# orig.net
KiCad netlist of a schematic drawn in EAGLE
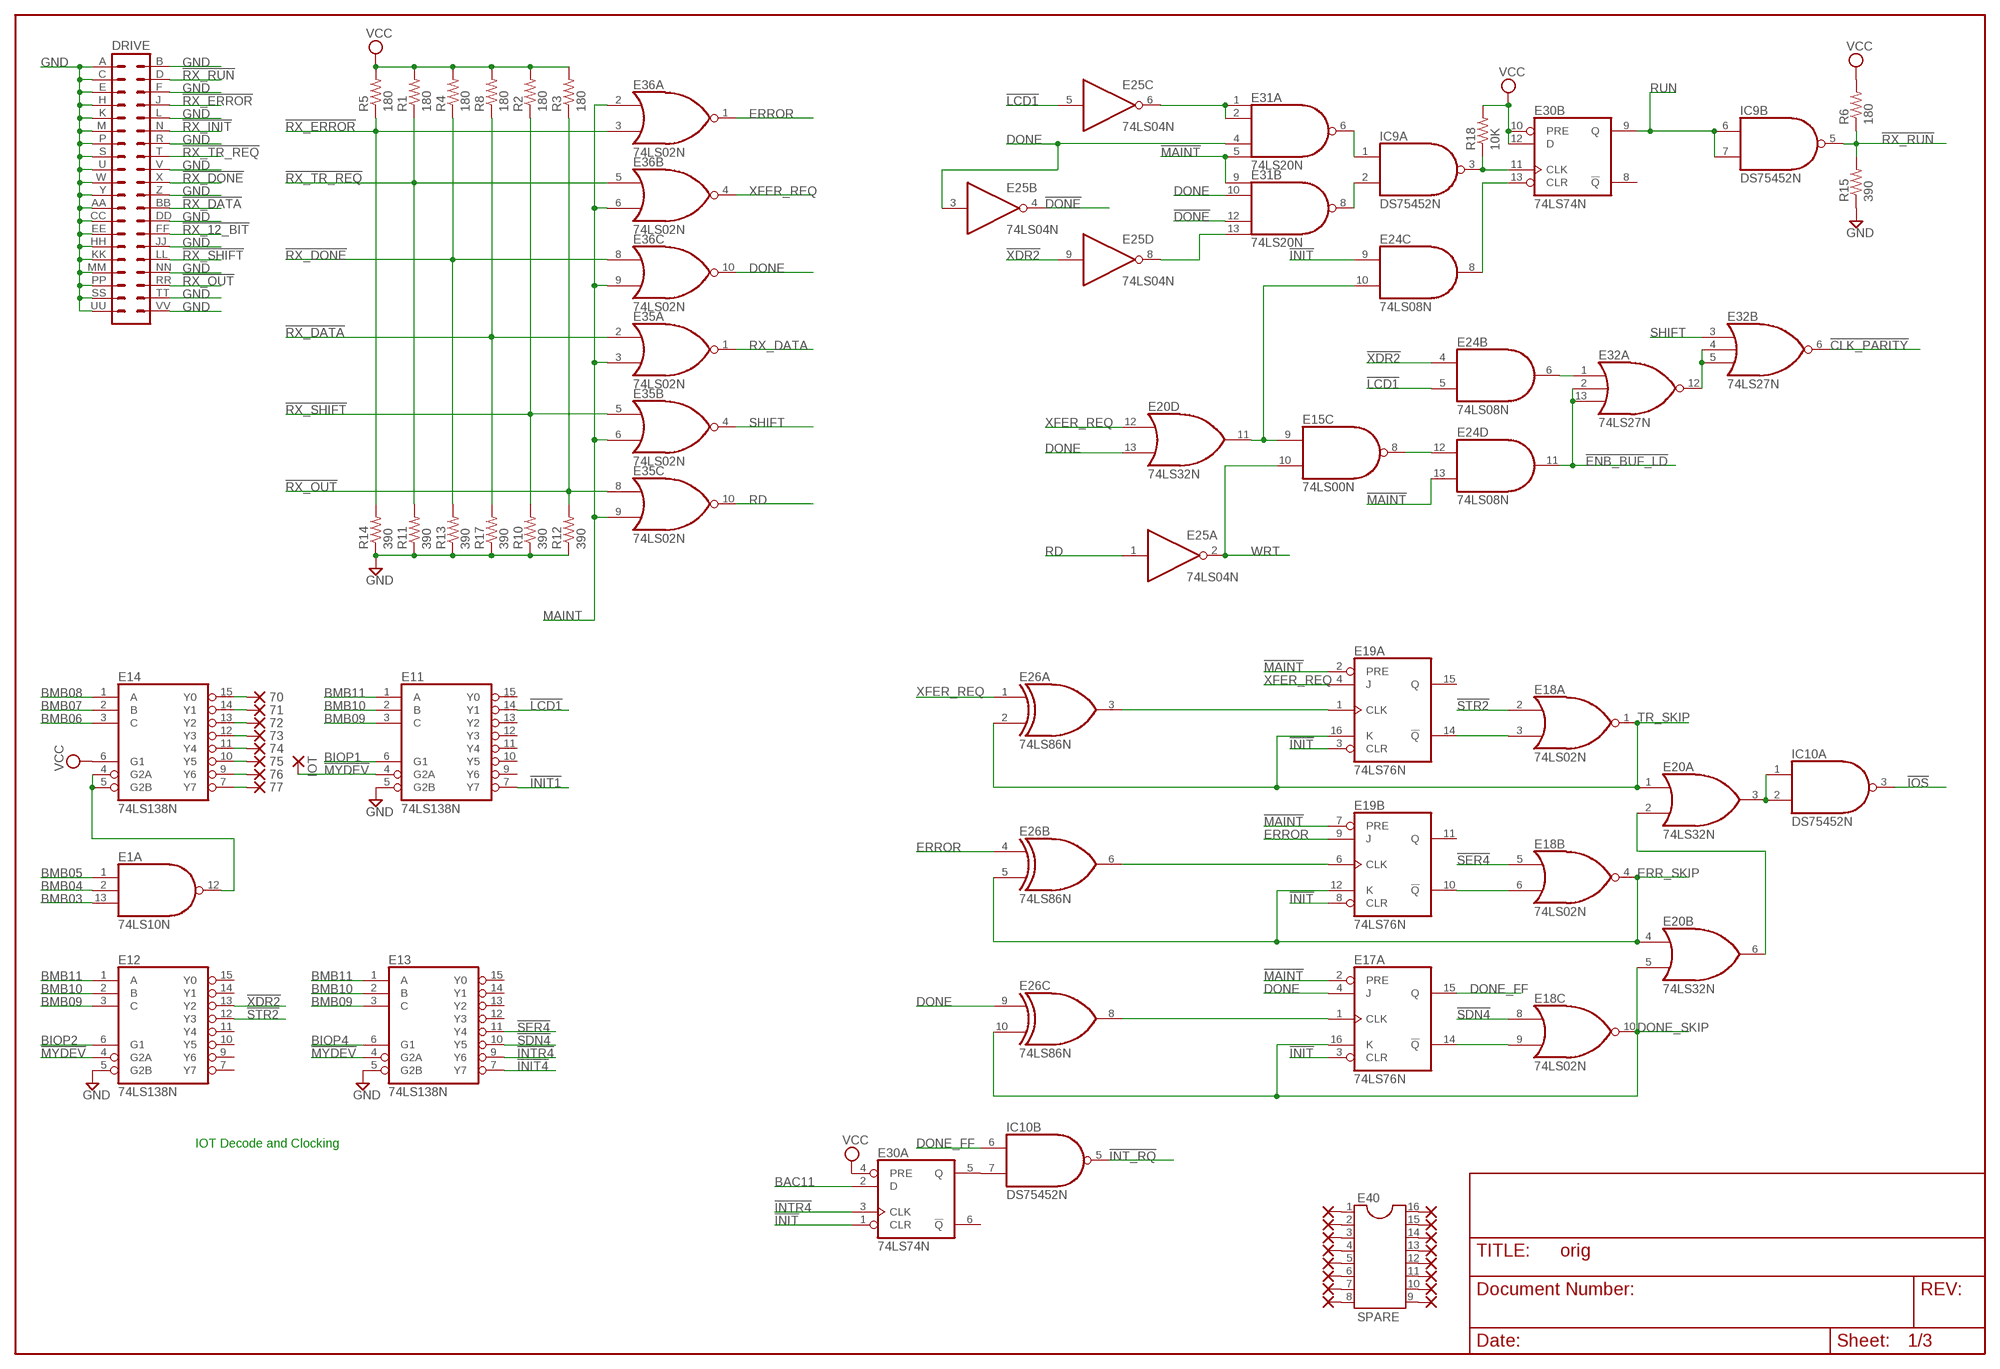
[diagram p0: schematic, sheet 1]
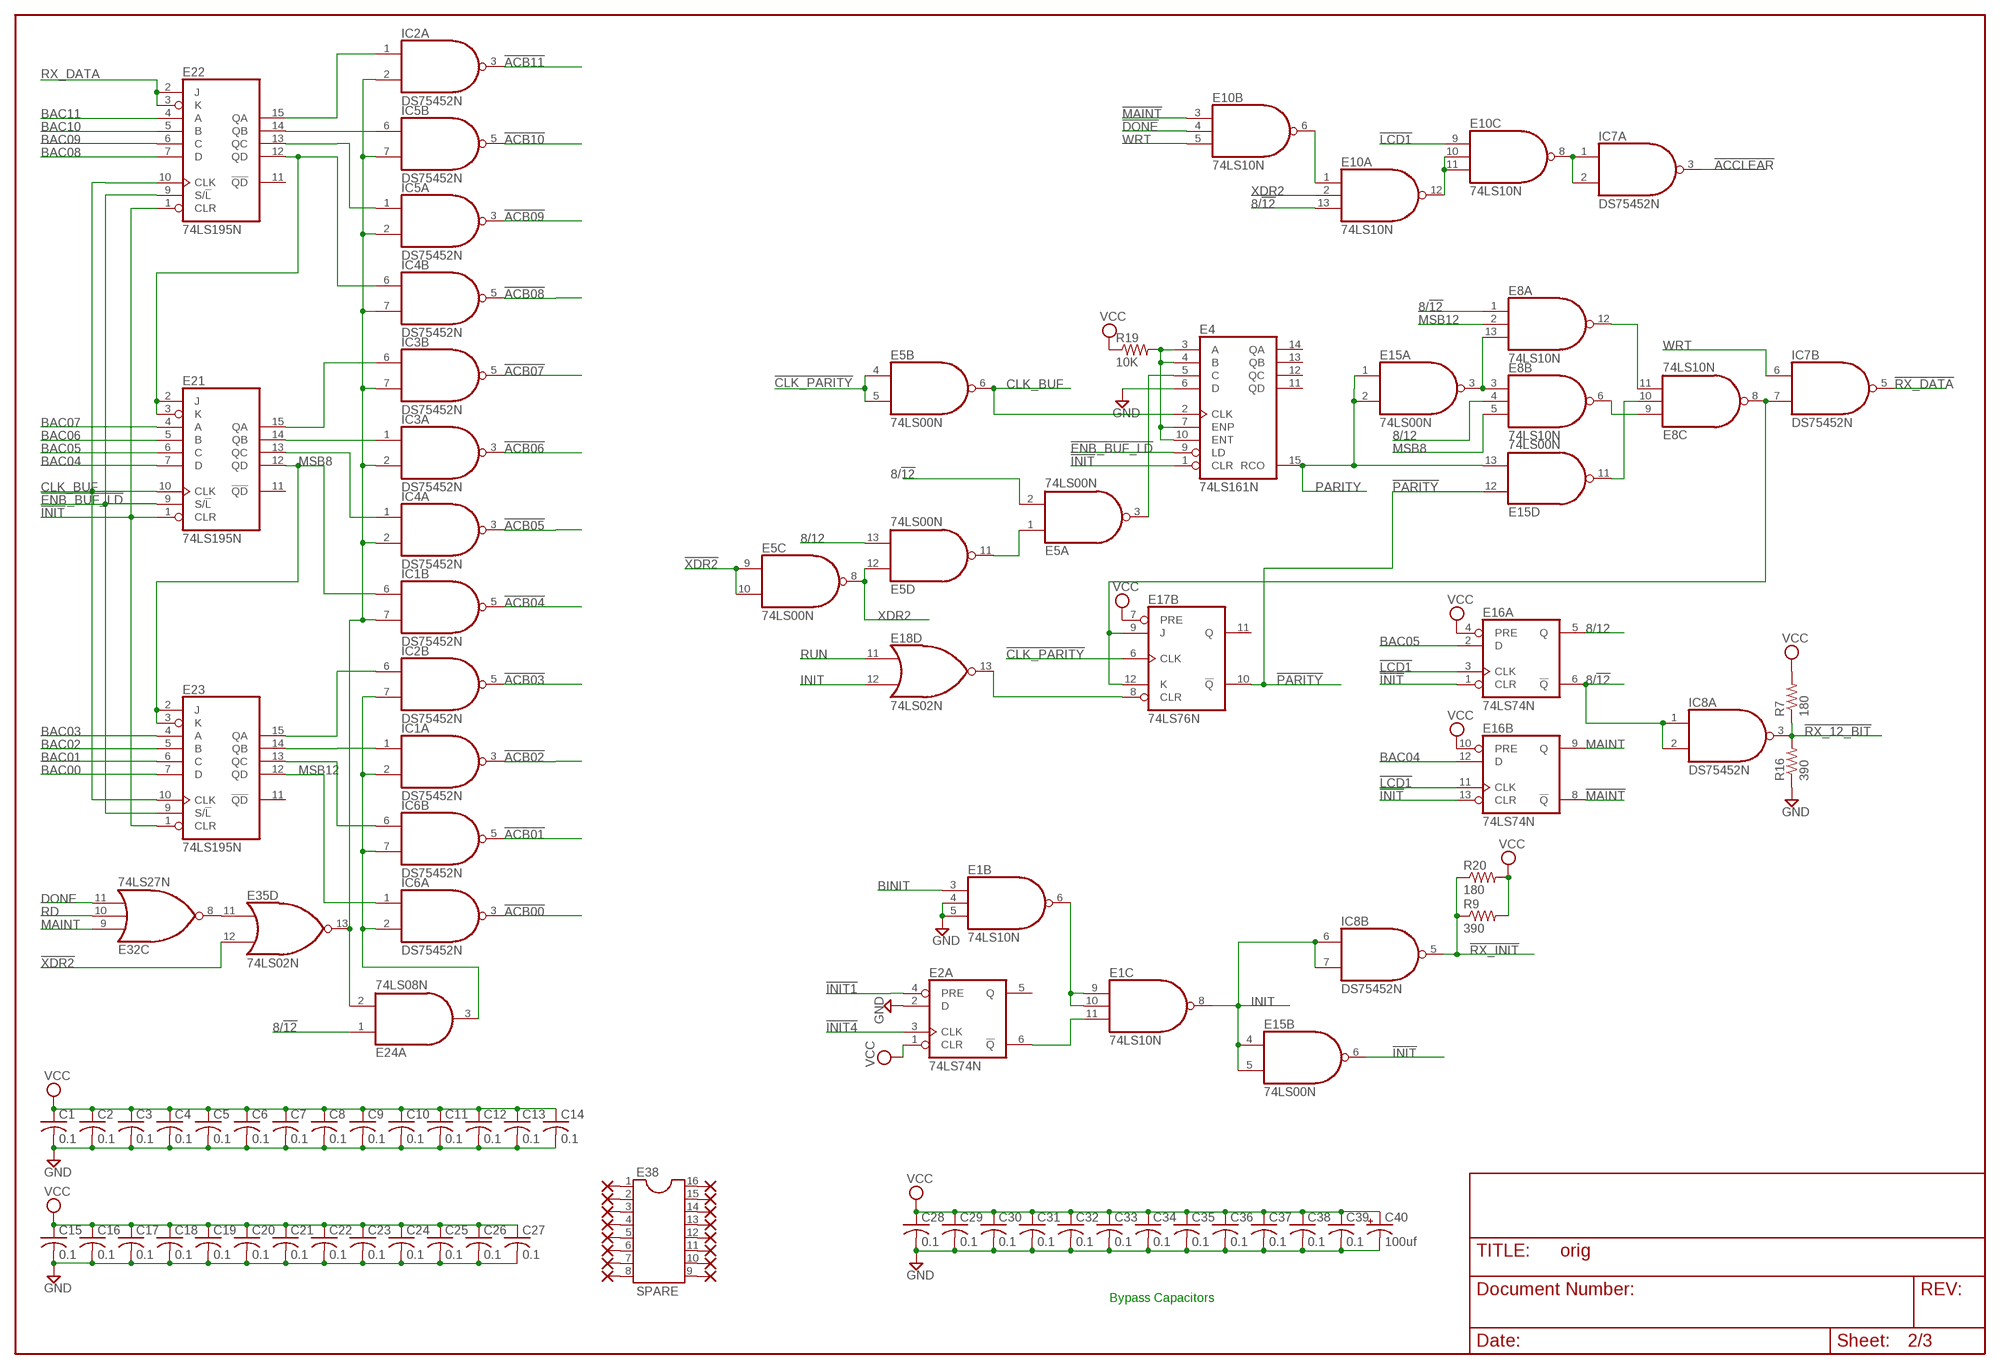
[diagram p1: schematic, sheet 2]
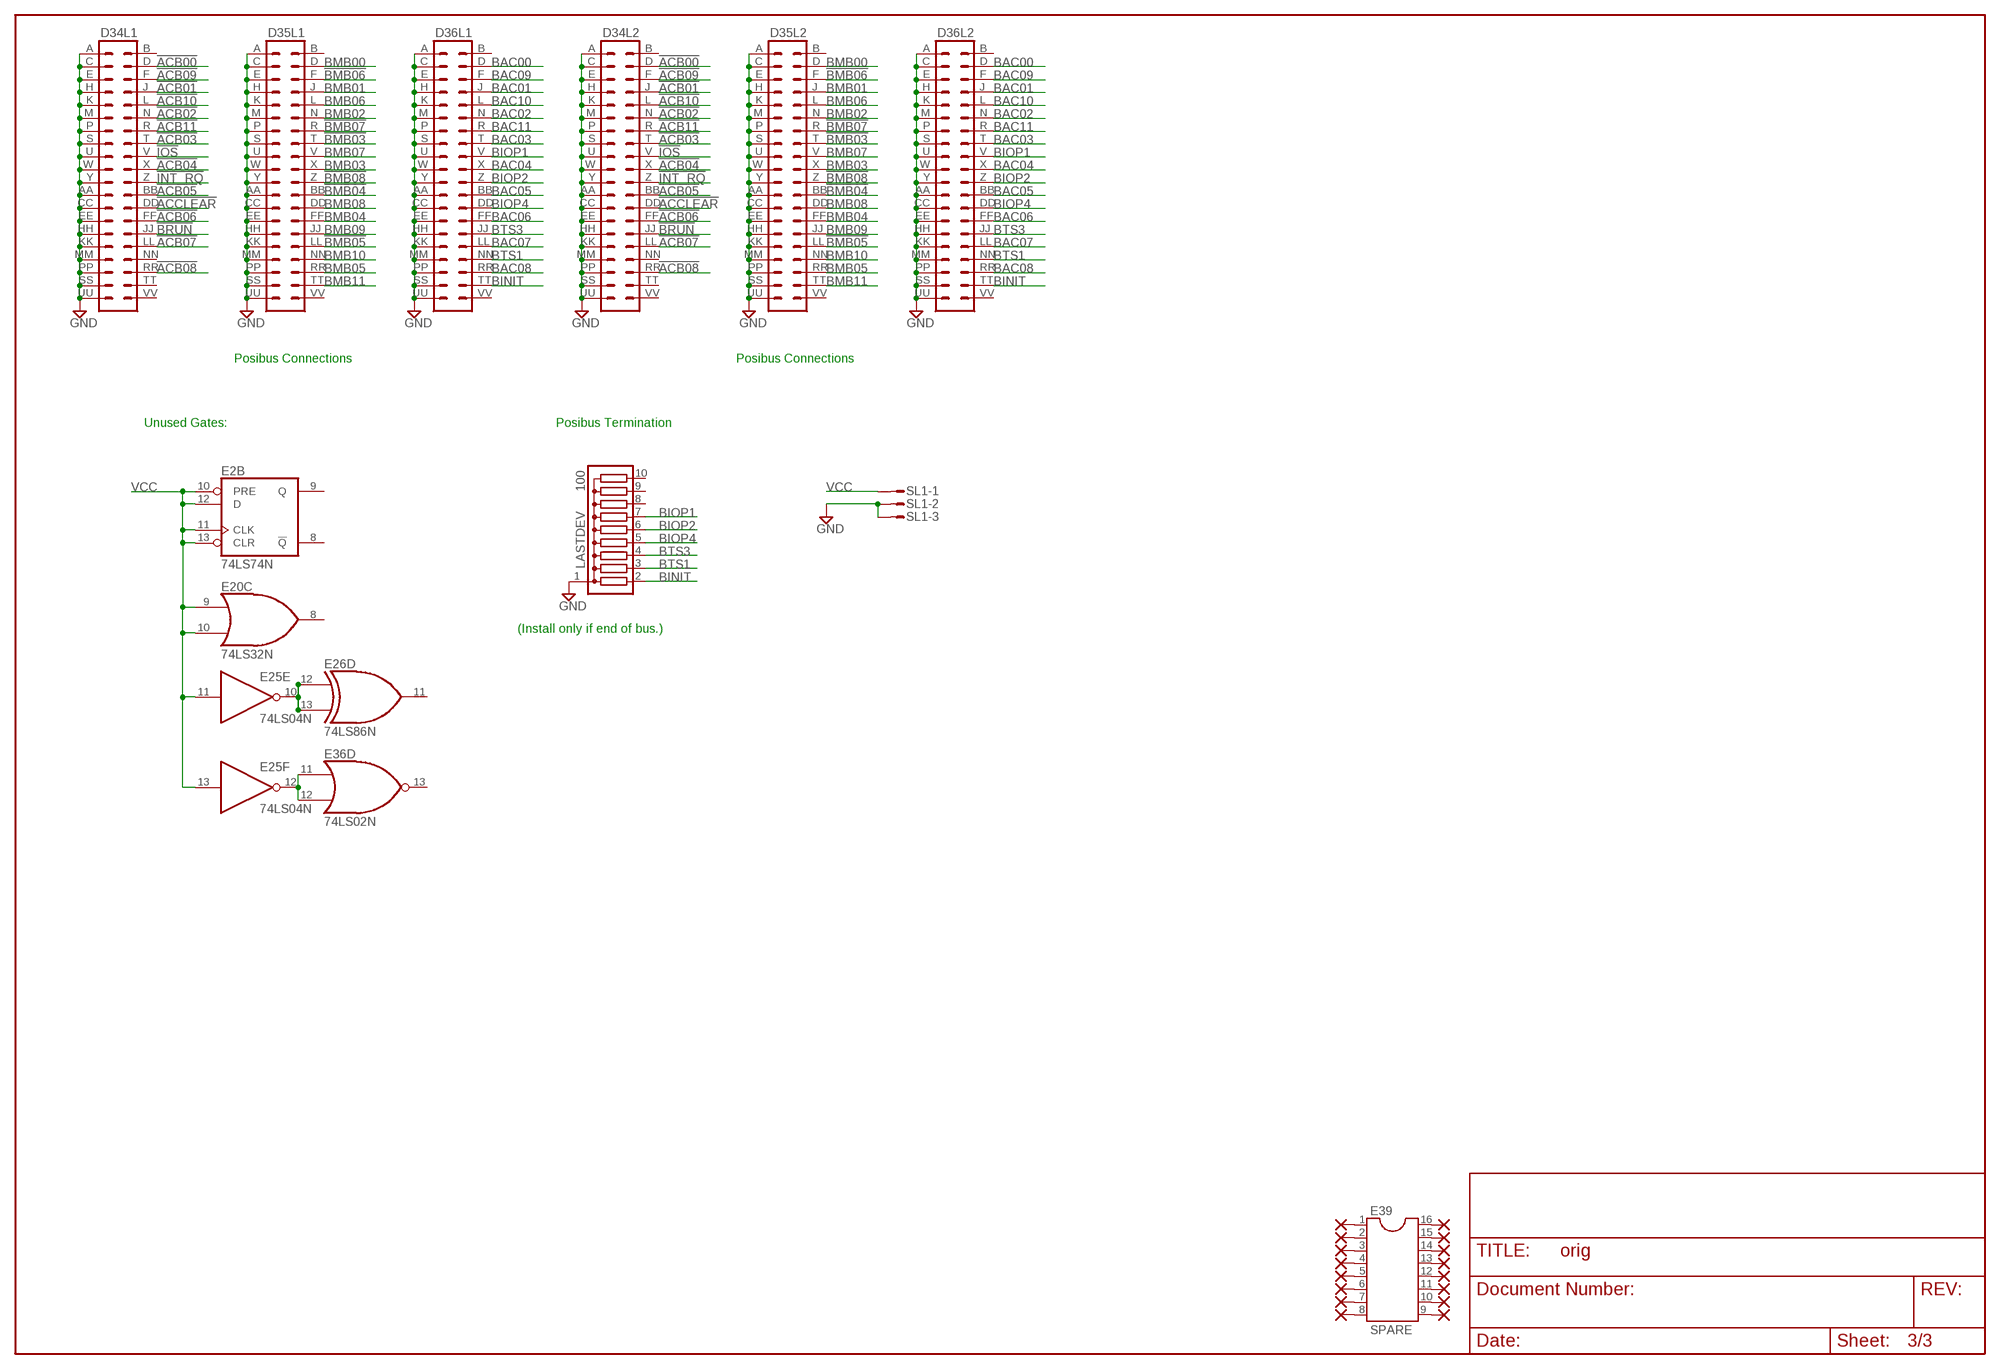
[diagram p2: schematic, sheet 3]

(export (version "E")
  (design (tool "Eeschema 10.0.6"))
  (components
    (comp (ref "70")
      (value "1,6/0,8")
      (footprint "eagle-import:1,6_0,8")
      (libsource (lib "eagle-import") (part "1,6/0,8"))
    )
    (comp (ref "71")
      (value "1,6/0,8")
      (footprint "eagle-import:1,6_0,8")
      (libsource (lib "eagle-import") (part "1,6/0,8"))
    )
    (comp (ref "72")
      (value "1,6/0,8")
      (footprint "eagle-import:1,6_0,8")
      (libsource (lib "eagle-import") (part "1,6/0,8"))
    )
    (comp (ref "73")
      (value "1,6/0,8")
      (footprint "eagle-import:1,6_0,8")
      (libsource (lib "eagle-import") (part "1,6/0,8"))
    )
    (comp (ref "74")
      (value "1,6/0,8")
      (footprint "eagle-import:1,6_0,8")
      (libsource (lib "eagle-import") (part "1,6/0,8"))
    )
    (comp (ref "75")
      (value "1,6/0,8")
      (footprint "eagle-import:1,6_0,8")
      (libsource (lib "eagle-import") (part "1,6/0,8"))
    )
    (comp (ref "76")
      (value "1,6/0,8")
      (footprint "eagle-import:1,6_0,8")
      (libsource (lib "eagle-import") (part "1,6/0,8"))
    )
    (comp (ref "77")
      (value "1,6/0,8")
      (footprint "eagle-import:1,6_0,8")
      (libsource (lib "eagle-import") (part "1,6/0,8"))
    )
    (comp (ref "DRIVE")
      (value "DEC40PIN")
      (footprint "eagle-import:DEC40PIN")
      (libsource (lib "eagle-import") (part "DEC40PIN"))
    )
    (comp (ref "E1")
      (value "74LS10N")
      (footprint "eagle-import:DIL14")
      (libsource (lib "eagle-import") (part "7410NLS"))
    )
    (comp (ref "E11")
      (value "74LS138N")
      (footprint "eagle-import:DIL16")
      (libsource (lib "eagle-import") (part "74138NLS"))
    )
    (comp (ref "E12")
      (value "74LS138N")
      (footprint "eagle-import:DIL16")
      (libsource (lib "eagle-import") (part "74138NLS"))
    )
    (comp (ref "E13")
      (value "74LS138N")
      (footprint "eagle-import:DIL16")
      (libsource (lib "eagle-import") (part "74138NLS"))
    )
    (comp (ref "E14")
      (value "74LS138N")
      (footprint "eagle-import:DIL16")
      (libsource (lib "eagle-import") (part "74138NLS"))
    )
    (comp (ref "E15")
      (value "74LS00N")
      (footprint "eagle-import:DIL14")
      (libsource (lib "eagle-import") (part "7400NLS"))
    )
    (comp (ref "E17")
      (value "74LS76N")
      (footprint "eagle-import:DIL16")
      (libsource (lib "eagle-import") (part "7476N"))
    )
    (comp (ref "E18")
      (value "74LS02N")
      (footprint "eagle-import:DIL14")
      (libsource (lib "eagle-import") (part "7402NLS"))
    )
    (comp (ref "E19")
      (value "74LS76N")
      (footprint "eagle-import:DIL16")
      (libsource (lib "eagle-import") (part "7476N"))
    )
    (comp (ref "E20")
      (value "74LS32N")
      (footprint "eagle-import:DIL14")
      (libsource (lib "eagle-import") (part "7432NLS"))
    )
    (comp (ref "E24")
      (value "74LS08N")
      (footprint "eagle-import:DIL14")
      (libsource (lib "eagle-import") (part "7408NLS"))
    )
    (comp (ref "E25")
      (value "74LS04N")
      (footprint "eagle-import:DIL14")
      (libsource (lib "eagle-import") (part "7404NLS"))
    )
    (comp (ref "E26")
      (value "74LS86N")
      (footprint "eagle-import:DIL14")
      (libsource (lib "eagle-import") (part "7486NLS"))
    )
    (comp (ref "E30")
      (value "74LS74N")
      (footprint "eagle-import:DIL14")
      (libsource (lib "eagle-import") (part "7474NLS"))
    )
    (comp (ref "E31")
      (value "74LS20N")
      (footprint "eagle-import:DIL14")
      (libsource (lib "eagle-import") (part "7420NLS"))
    )
    (comp (ref "E32")
      (value "74LS27N")
      (footprint "eagle-import:DIL14")
      (libsource (lib "eagle-import") (part "7427NLS"))
    )
    (comp (ref "E35")
      (value "74LS02N")
      (footprint "eagle-import:DIL14")
      (libsource (lib "eagle-import") (part "7402NLS"))
    )
    (comp (ref "E36")
      (value "74LS02N")
      (footprint "eagle-import:DIL14")
      (libsource (lib "eagle-import") (part "7402NLS"))
    )
    (comp (ref "E40")
      (value "SPARE")
      (footprint "eagle-import:DIL16")
      (libsource (lib "eagle-import") (part "DIL16"))
    )
    (comp (ref "IC9")
      (value "DS75452N")
      (footprint "eagle-import:DIL08")
      (libsource (lib "eagle-import") (part "DS75452N"))
    )
    (comp (ref "IC10")
      (value "DS75452N")
      (footprint "eagle-import:DIL08")
      (libsource (lib "eagle-import") (part "DS75452N"))
    )
    (comp (ref "IOT")
      (value "1,6/0,8")
      (footprint "eagle-import:1,6_0,8")
      (libsource (lib "eagle-import") (part "1,6/0,8"))
    )
    (comp (ref "PAD18")
      (value "1,6/0,8")
      (footprint "eagle-import:1,6_0,8")
      (libsource (lib "eagle-import") (part "1,6/0,8"))
    )
    (comp (ref "PAD19")
      (value "1,6/0,8")
      (footprint "eagle-import:1,6_0,8")
      (libsource (lib "eagle-import") (part "1,6/0,8"))
    )
    (comp (ref "PAD28")
      (value "1,6/0,8")
      (footprint "eagle-import:1,6_0,8")
      (libsource (lib "eagle-import") (part "1,6/0,8"))
    )
    (comp (ref "PAD29")
      (value "1,6/0,8")
      (footprint "eagle-import:1,6_0,8")
      (libsource (lib "eagle-import") (part "1,6/0,8"))
    )
    (comp (ref "PAD30")
      (value "1,6/0,8")
      (footprint "eagle-import:1,6_0,8")
      (libsource (lib "eagle-import") (part "1,6/0,8"))
    )
    (comp (ref "PAD31")
      (value "1,6/0,8")
      (footprint "eagle-import:1,6_0,8")
      (libsource (lib "eagle-import") (part "1,6/0,8"))
    )
    (comp (ref "PAD32")
      (value "1,6/0,8")
      (footprint "eagle-import:1,6_0,8")
      (libsource (lib "eagle-import") (part "1,6/0,8"))
    )
    (comp (ref "PAD33")
      (value "1,6/0,8")
      (footprint "eagle-import:1,6_0,8")
      (libsource (lib "eagle-import") (part "1,6/0,8"))
    )
    (comp (ref "PAD34")
      (value "1,6/0,8")
      (footprint "eagle-import:1,6_0,8")
      (libsource (lib "eagle-import") (part "1,6/0,8"))
    )
    (comp (ref "PAD35")
      (value "1,6/0,8")
      (footprint "eagle-import:1,6_0,8")
      (libsource (lib "eagle-import") (part "1,6/0,8"))
    )
    (comp (ref "PAD36")
      (value "1,6/0,8")
      (footprint "eagle-import:1,6_0,8")
      (libsource (lib "eagle-import") (part "1,6/0,8"))
    )
    (comp (ref "PAD37")
      (value "1,6/0,8")
      (footprint "eagle-import:1,6_0,8")
      (libsource (lib "eagle-import") (part "1,6/0,8"))
    )
    (comp (ref "PAD38")
      (value "1,6/0,8")
      (footprint "eagle-import:1,6_0,8")
      (libsource (lib "eagle-import") (part "1,6/0,8"))
    )
    (comp (ref "PAD39")
      (value "1,6/0,8")
      (footprint "eagle-import:1,6_0,8")
      (libsource (lib "eagle-import") (part "1,6/0,8"))
    )
    (comp (ref "PAD40")
      (value "1,6/0,8")
      (footprint "eagle-import:1,6_0,8")
      (libsource (lib "eagle-import") (part "1,6/0,8"))
    )
    (comp (ref "PAD41")
      (value "1,6/0,8")
      (footprint "eagle-import:1,6_0,8")
      (libsource (lib "eagle-import") (part "1,6/0,8"))
    )
    (comp (ref "R1")
      (value "180")
      (footprint "eagle-import:0207_10")
      (libsource (lib "eagle-import") (part "R-US_0207/10"))
    )
    (comp (ref "R2")
      (value "180")
      (footprint "eagle-import:0207_10")
      (libsource (lib "eagle-import") (part "R-US_0207/10"))
    )
    (comp (ref "R3")
      (value "180")
      (footprint "eagle-import:0207_10")
      (libsource (lib "eagle-import") (part "R-US_0207/10"))
    )
    (comp (ref "R4")
      (value "180")
      (footprint "eagle-import:0207_10")
      (libsource (lib "eagle-import") (part "R-US_0207/10"))
    )
    (comp (ref "R5")
      (value "180")
      (footprint "eagle-import:0207_10")
      (libsource (lib "eagle-import") (part "R-US_0207/10"))
    )
    (comp (ref "R6")
      (value "180")
      (footprint "eagle-import:0207_10")
      (libsource (lib "eagle-import") (part "R-US_0207/10"))
    )
    (comp (ref "R8")
      (value "180")
      (footprint "eagle-import:0207_10")
      (libsource (lib "eagle-import") (part "R-US_0207/10"))
    )
    (comp (ref "R10")
      (value "390")
      (footprint "eagle-import:0207_10")
      (libsource (lib "eagle-import") (part "R-US_0207/10"))
    )
    (comp (ref "R11")
      (value "390")
      (footprint "eagle-import:0207_10")
      (libsource (lib "eagle-import") (part "R-US_0207/10"))
    )
    (comp (ref "R12")
      (value "390")
      (footprint "eagle-import:0207_10")
      (libsource (lib "eagle-import") (part "R-US_0207/10"))
    )
    (comp (ref "R13")
      (value "390")
      (footprint "eagle-import:0207_10")
      (libsource (lib "eagle-import") (part "R-US_0207/10"))
    )
    (comp (ref "R14")
      (value "390")
      (footprint "eagle-import:0207_10")
      (libsource (lib "eagle-import") (part "R-US_0207/10"))
    )
    (comp (ref "R15")
      (value "390")
      (footprint "eagle-import:0207_10")
      (libsource (lib "eagle-import") (part "R-US_0207/10"))
    )
    (comp (ref "R17")
      (value "390")
      (footprint "eagle-import:0207_10")
      (libsource (lib "eagle-import") (part "R-US_0207/10"))
    )
    (comp (ref "R18")
      (value "10K")
      (footprint "eagle-import:0207_10")
      (libsource (lib "eagle-import") (part "R-US_0207/10"))
    )
    (comp (ref "C1")
      (value "0.1")
      (footprint "eagle-import:C050-025X075")
      (libsource (lib "eagle-import") (part "C-US050-025X075"))
    )
    (comp (ref "C2")
      (value "0.1")
      (footprint "eagle-import:C050-025X075")
      (libsource (lib "eagle-import") (part "C-US050-025X075"))
    )
    (comp (ref "C3")
      (value "0.1")
      (footprint "eagle-import:C050-025X075")
      (libsource (lib "eagle-import") (part "C-US050-025X075"))
    )
    (comp (ref "C4")
      (value "0.1")
      (footprint "eagle-import:C050-025X075")
      (libsource (lib "eagle-import") (part "C-US050-025X075"))
    )
    (comp (ref "C5")
      (value "0.1")
      (footprint "eagle-import:C050-025X075")
      (libsource (lib "eagle-import") (part "C-US050-025X075"))
    )
    (comp (ref "C6")
      (value "0.1")
      (footprint "eagle-import:C050-025X075")
      (libsource (lib "eagle-import") (part "C-US050-025X075"))
    )
    (comp (ref "C7")
      (value "0.1")
      (footprint "eagle-import:C050-025X075")
      (libsource (lib "eagle-import") (part "C-US050-025X075"))
    )
    (comp (ref "C8")
      (value "0.1")
      (footprint "eagle-import:C050-025X075")
      (libsource (lib "eagle-import") (part "C-US050-025X075"))
    )
    (comp (ref "C9")
      (value "0.1")
      (footprint "eagle-import:C050-025X075")
      (libsource (lib "eagle-import") (part "C-US050-025X075"))
    )
    (comp (ref "C10")
      (value "0.1")
      (footprint "eagle-import:C050-025X075")
      (libsource (lib "eagle-import") (part "C-US050-025X075"))
    )
    (comp (ref "C11")
      (value "0.1")
      (footprint "eagle-import:C050-025X075")
      (libsource (lib "eagle-import") (part "C-US050-025X075"))
    )
    (comp (ref "C12")
      (value "0.1")
      (footprint "eagle-import:C050-025X075")
      (libsource (lib "eagle-import") (part "C-US050-025X075"))
    )
    (comp (ref "C13")
      (value "0.1")
      (footprint "eagle-import:C050-025X075")
      (libsource (lib "eagle-import") (part "C-US050-025X075"))
    )
    (comp (ref "C14")
      (value "0.1")
      (footprint "eagle-import:C050-025X075")
      (libsource (lib "eagle-import") (part "C-US050-025X075"))
    )
    (comp (ref "C15")
      (value "0.1")
      (footprint "eagle-import:C050-025X075")
      (libsource (lib "eagle-import") (part "C-US050-025X075"))
    )
    (comp (ref "C16")
      (value "0.1")
      (footprint "eagle-import:C050-025X075")
      (libsource (lib "eagle-import") (part "C-US050-025X075"))
    )
    (comp (ref "C17")
      (value "0.1")
      (footprint "eagle-import:C050-025X075")
      (libsource (lib "eagle-import") (part "C-US050-025X075"))
    )
    (comp (ref "C18")
      (value "0.1")
      (footprint "eagle-import:C050-025X075")
      (libsource (lib "eagle-import") (part "C-US050-025X075"))
    )
    (comp (ref "C19")
      (value "0.1")
      (footprint "eagle-import:C050-025X075")
      (libsource (lib "eagle-import") (part "C-US050-025X075"))
    )
    (comp (ref "C20")
      (value "0.1")
      (footprint "eagle-import:C050-025X075")
      (libsource (lib "eagle-import") (part "C-US050-025X075"))
    )
    (comp (ref "C21")
      (value "0.1")
      (footprint "eagle-import:C050-025X075")
      (libsource (lib "eagle-import") (part "C-US050-025X075"))
    )
    (comp (ref "C22")
      (value "0.1")
      (footprint "eagle-import:C050-025X075")
      (libsource (lib "eagle-import") (part "C-US050-025X075"))
    )
    (comp (ref "C23")
      (value "0.1")
      (footprint "eagle-import:C050-025X075")
      (libsource (lib "eagle-import") (part "C-US050-025X075"))
    )
    (comp (ref "C24")
      (value "0.1")
      (footprint "eagle-import:C050-025X075")
      (libsource (lib "eagle-import") (part "C-US050-025X075"))
    )
    (comp (ref "C25")
      (value "0.1")
      (footprint "eagle-import:C050-025X075")
      (libsource (lib "eagle-import") (part "C-US050-025X075"))
    )
    (comp (ref "C26")
      (value "0.1")
      (footprint "eagle-import:C050-025X075")
      (libsource (lib "eagle-import") (part "C-US050-025X075"))
    )
    (comp (ref "C27")
      (value "0.1")
      (footprint "eagle-import:C050-025X075")
      (libsource (lib "eagle-import") (part "C-US050-025X075"))
    )
    (comp (ref "C28")
      (value "0.1")
      (footprint "eagle-import:C050-025X075")
      (libsource (lib "eagle-import") (part "C-US050-025X075"))
    )
    (comp (ref "C29")
      (value "0.1")
      (footprint "eagle-import:C050-025X075")
      (libsource (lib "eagle-import") (part "C-US050-025X075"))
    )
    (comp (ref "C30")
      (value "0.1")
      (footprint "eagle-import:C050-025X075")
      (libsource (lib "eagle-import") (part "C-US050-025X075"))
    )
    (comp (ref "C31")
      (value "0.1")
      (footprint "eagle-import:C050-025X075")
      (libsource (lib "eagle-import") (part "C-US050-025X075"))
    )
    (comp (ref "C32")
      (value "0.1")
      (footprint "eagle-import:C050-025X075")
      (libsource (lib "eagle-import") (part "C-US050-025X075"))
    )
    (comp (ref "C33")
      (value "0.1")
      (footprint "eagle-import:C050-025X075")
      (libsource (lib "eagle-import") (part "C-US050-025X075"))
    )
    (comp (ref "C34")
      (value "0.1")
      (footprint "eagle-import:C050-025X075")
      (libsource (lib "eagle-import") (part "C-US050-025X075"))
    )
    (comp (ref "C35")
      (value "0.1")
      (footprint "eagle-import:C050-025X075")
      (libsource (lib "eagle-import") (part "C-US050-025X075"))
    )
    (comp (ref "C36")
      (value "0.1")
      (footprint "eagle-import:C050-025X075")
      (libsource (lib "eagle-import") (part "C-US050-025X075"))
    )
    (comp (ref "C37")
      (value "0.1")
      (footprint "eagle-import:C050-025X075")
      (libsource (lib "eagle-import") (part "C-US050-025X075"))
    )
    (comp (ref "C38")
      (value "0.1")
      (footprint "eagle-import:C050-025X075")
      (libsource (lib "eagle-import") (part "C-US050-025X075"))
    )
    (comp (ref "C39")
      (value "0.1")
      (footprint "eagle-import:C050-025X075")
      (libsource (lib "eagle-import") (part "C-US050-025X075"))
    )
    (comp (ref "C40")
      (value "100uf")
      (footprint "eagle-import:E22-9")
      (libsource (lib "eagle-import") (part "CPOL-USE22-9AXIAL"))
    )
    (comp (ref "E2")
      (value "74LS74N")
      (footprint "eagle-import:DIL14")
      (libsource (lib "eagle-import") (part "7474NLS"))
    )
    (comp (ref "E4")
      (value "74LS161N")
      (footprint "eagle-import:DIL16")
      (libsource (lib "eagle-import") (part "74161NLS"))
    )
    (comp (ref "E5")
      (value "74LS00N")
      (footprint "eagle-import:DIL14")
      (libsource (lib "eagle-import") (part "7400NLS"))
    )
    (comp (ref "E8")
      (value "74LS10N")
      (footprint "eagle-import:DIL14")
      (libsource (lib "eagle-import") (part "7410NLS"))
    )
    (comp (ref "E10")
      (value "74LS10N")
      (footprint "eagle-import:DIL14")
      (libsource (lib "eagle-import") (part "7410NLS"))
    )
    (comp (ref "E16")
      (value "74LS74N")
      (footprint "eagle-import:DIL14")
      (libsource (lib "eagle-import") (part "7474NLS"))
    )
    (comp (ref "E21")
      (value "74LS195N")
      (footprint "eagle-import:DIL16")
      (libsource (lib "eagle-import") (part "74195NLS"))
    )
    (comp (ref "E22")
      (value "74LS195N")
      (footprint "eagle-import:DIL16")
      (libsource (lib "eagle-import") (part "74195NLS"))
    )
    (comp (ref "E23")
      (value "74LS195N")
      (footprint "eagle-import:DIL16")
      (libsource (lib "eagle-import") (part "74195NLS"))
    )
    (comp (ref "E38")
      (value "SPARE")
      (footprint "eagle-import:DIL16")
      (libsource (lib "eagle-import") (part "DIL16"))
    )
    (comp (ref "IC1")
      (value "DS75452N")
      (footprint "eagle-import:DIL08")
      (libsource (lib "eagle-import") (part "DS75452N"))
    )
    (comp (ref "IC2")
      (value "DS75452N")
      (footprint "eagle-import:DIL08")
      (libsource (lib "eagle-import") (part "DS75452N"))
    )
    (comp (ref "IC3")
      (value "DS75452N")
      (footprint "eagle-import:DIL08")
      (libsource (lib "eagle-import") (part "DS75452N"))
    )
    (comp (ref "IC4")
      (value "DS75452N")
      (footprint "eagle-import:DIL08")
      (libsource (lib "eagle-import") (part "DS75452N"))
    )
    (comp (ref "IC5")
      (value "DS75452N")
      (footprint "eagle-import:DIL08")
      (libsource (lib "eagle-import") (part "DS75452N"))
    )
    (comp (ref "IC6")
      (value "DS75452N")
      (footprint "eagle-import:DIL08")
      (libsource (lib "eagle-import") (part "DS75452N"))
    )
    (comp (ref "IC7")
      (value "DS75452N")
      (footprint "eagle-import:DIL08")
      (libsource (lib "eagle-import") (part "DS75452N"))
    )
    (comp (ref "IC8")
      (value "DS75452N")
      (footprint "eagle-import:DIL08")
      (libsource (lib "eagle-import") (part "DS75452N"))
    )
    (comp (ref "PAD10")
      (value "1,6/0,8")
      (footprint "eagle-import:1,6_0,8")
      (libsource (lib "eagle-import") (part "1,6/0,8"))
    )
    (comp (ref "PAD11")
      (value "1,6/0,8")
      (footprint "eagle-import:1,6_0,8")
      (libsource (lib "eagle-import") (part "1,6/0,8"))
    )
    (comp (ref "PAD12")
      (value "1,6/0,8")
      (footprint "eagle-import:1,6_0,8")
      (libsource (lib "eagle-import") (part "1,6/0,8"))
    )
    (comp (ref "PAD13")
      (value "1,6/0,8")
      (footprint "eagle-import:1,6_0,8")
      (libsource (lib "eagle-import") (part "1,6/0,8"))
    )
    (comp (ref "PAD14")
      (value "1,6/0,8")
      (footprint "eagle-import:1,6_0,8")
      (libsource (lib "eagle-import") (part "1,6/0,8"))
    )
    (comp (ref "PAD15")
      (value "1,6/0,8")
      (footprint "eagle-import:1,6_0,8")
      (libsource (lib "eagle-import") (part "1,6/0,8"))
    )
    (comp (ref "PAD16")
      (value "1,6/0,8")
      (footprint "eagle-import:1,6_0,8")
      (libsource (lib "eagle-import") (part "1,6/0,8"))
    )
    (comp (ref "PAD17")
      (value "1,6/0,8")
      (footprint "eagle-import:1,6_0,8")
      (libsource (lib "eagle-import") (part "1,6/0,8"))
    )
    (comp (ref "PAD20")
      (value "1,6/0,8")
      (footprint "eagle-import:1,6_0,8")
      (libsource (lib "eagle-import") (part "1,6/0,8"))
    )
    (comp (ref "PAD21")
      (value "1,6/0,8")
      (footprint "eagle-import:1,6_0,8")
      (libsource (lib "eagle-import") (part "1,6/0,8"))
    )
    (comp (ref "PAD22")
      (value "1,6/0,8")
      (footprint "eagle-import:1,6_0,8")
      (libsource (lib "eagle-import") (part "1,6/0,8"))
    )
    (comp (ref "PAD23")
      (value "1,6/0,8")
      (footprint "eagle-import:1,6_0,8")
      (libsource (lib "eagle-import") (part "1,6/0,8"))
    )
    (comp (ref "PAD24")
      (value "1,6/0,8")
      (footprint "eagle-import:1,6_0,8")
      (libsource (lib "eagle-import") (part "1,6/0,8"))
    )
    (comp (ref "PAD25")
      (value "1,6/0,8")
      (footprint "eagle-import:1,6_0,8")
      (libsource (lib "eagle-import") (part "1,6/0,8"))
    )
    (comp (ref "PAD26")
      (value "1,6/0,8")
      (footprint "eagle-import:1,6_0,8")
      (libsource (lib "eagle-import") (part "1,6/0,8"))
    )
    (comp (ref "PAD27")
      (value "1,6/0,8")
      (footprint "eagle-import:1,6_0,8")
      (libsource (lib "eagle-import") (part "1,6/0,8"))
    )
    (comp (ref "R7")
      (value "180")
      (footprint "eagle-import:0207_10")
      (libsource (lib "eagle-import") (part "R-US_0207/10"))
    )
    (comp (ref "R9")
      (value "390")
      (footprint "eagle-import:0207_10")
      (libsource (lib "eagle-import") (part "R-US_0207/10"))
    )
    (comp (ref "R16")
      (value "390")
      (footprint "eagle-import:0207_10")
      (libsource (lib "eagle-import") (part "R-US_0207/10"))
    )
    (comp (ref "R19")
      (value "10K")
      (footprint "eagle-import:0207_10")
      (libsource (lib "eagle-import") (part "R-US_0207/10"))
    )
    (comp (ref "R20")
      (value "180")
      (footprint "eagle-import:0207_10")
      (libsource (lib "eagle-import") (part "R-US_0207/10"))
    )
    (comp (ref "D34L1")
      (value "DEC40PIN")
      (footprint "eagle-import:DEC40PIN")
      (libsource (lib "eagle-import") (part "DEC40PIN"))
    )
    (comp (ref "D34L2")
      (value "DEC40PIN")
      (footprint "eagle-import:DEC40PIN")
      (libsource (lib "eagle-import") (part "DEC40PIN"))
    )
    (comp (ref "D35L1")
      (value "DEC40PIN")
      (footprint "eagle-import:DEC40PIN")
      (libsource (lib "eagle-import") (part "DEC40PIN"))
    )
    (comp (ref "D35L2")
      (value "DEC40PIN")
      (footprint "eagle-import:DEC40PIN")
      (libsource (lib "eagle-import") (part "DEC40PIN"))
    )
    (comp (ref "D36L1")
      (value "DEC40PIN")
      (footprint "eagle-import:DEC40PIN")
      (libsource (lib "eagle-import") (part "DEC40PIN"))
    )
    (comp (ref "D36L2")
      (value "DEC40PIN")
      (footprint "eagle-import:DEC40PIN")
      (libsource (lib "eagle-import") (part "DEC40PIN"))
    )
    (comp (ref "E39")
      (value "SPARE")
      (footprint "eagle-import:DIL16")
      (libsource (lib "eagle-import") (part "DIL16"))
    )
    (comp (ref "LASTDEV")
      (value "100")
      (footprint "eagle-import:SIL10")
      (libsource (lib "eagle-import") (part "G09R"))
    )
    (comp (ref "PAD42")
      (value "1,6/0,8")
      (footprint "eagle-import:1,6_0,8")
      (libsource (lib "eagle-import") (part "1,6/0,8"))
    )
    (comp (ref "PAD43")
      (value "1,6/0,8")
      (footprint "eagle-import:1,6_0,8")
      (libsource (lib "eagle-import") (part "1,6/0,8"))
    )
    (comp (ref "PAD44")
      (value "1,6/0,8")
      (footprint "eagle-import:1,6_0,8")
      (libsource (lib "eagle-import") (part "1,6/0,8"))
    )
    (comp (ref "PAD45")
      (value "1,6/0,8")
      (footprint "eagle-import:1,6_0,8")
      (libsource (lib "eagle-import") (part "1,6/0,8"))
    )
    (comp (ref "PAD46")
      (value "1,6/0,8")
      (footprint "eagle-import:1,6_0,8")
      (libsource (lib "eagle-import") (part "1,6/0,8"))
    )
    (comp (ref "PAD47")
      (value "1,6/0,8")
      (footprint "eagle-import:1,6_0,8")
      (libsource (lib "eagle-import") (part "1,6/0,8"))
    )
    (comp (ref "PAD48")
      (value "1,6/0,8")
      (footprint "eagle-import:1,6_0,8")
      (libsource (lib "eagle-import") (part "1,6/0,8"))
    )
    (comp (ref "PAD49")
      (value "1,6/0,8")
      (footprint "eagle-import:1,6_0,8")
      (libsource (lib "eagle-import") (part "1,6/0,8"))
    )
    (comp (ref "PAD50")
      (value "1,6/0,8")
      (footprint "eagle-import:1,6_0,8")
      (libsource (lib "eagle-import") (part "1,6/0,8"))
    )
    (comp (ref "PAD51")
      (value "1,6/0,8")
      (footprint "eagle-import:1,6_0,8")
      (libsource (lib "eagle-import") (part "1,6/0,8"))
    )
    (comp (ref "PAD52")
      (value "1,6/0,8")
      (footprint "eagle-import:1,6_0,8")
      (libsource (lib "eagle-import") (part "1,6/0,8"))
    )
    (comp (ref "PAD53")
      (value "1,6/0,8")
      (footprint "eagle-import:1,6_0,8")
      (libsource (lib "eagle-import") (part "1,6/0,8"))
    )
    (comp (ref "PAD54")
      (value "1,6/0,8")
      (footprint "eagle-import:1,6_0,8")
      (libsource (lib "eagle-import") (part "1,6/0,8"))
    )
    (comp (ref "PAD55")
      (value "1,6/0,8")
      (footprint "eagle-import:1,6_0,8")
      (libsource (lib "eagle-import") (part "1,6/0,8"))
    )
    (comp (ref "PAD56")
      (value "1,6/0,8")
      (footprint "eagle-import:1,6_0,8")
      (libsource (lib "eagle-import") (part "1,6/0,8"))
    )
    (comp (ref "PAD57")
      (value "1,6/0,8")
      (footprint "eagle-import:1,6_0,8")
      (libsource (lib "eagle-import") (part "1,6/0,8"))
    )
    (comp (ref "SL1")
      (value "MA04S")
      (footprint "eagle-import:04PA")
      (libsource (lib "eagle-import") (part "MA04S"))
    )
  )
  (nets
    (net (code "1") (name "8{slash}12") (class "Default")
      (node (ref "E16") (pin "5") (pinfunction "Q_5") (pintype "output"))
      (node (ref "E5") (pin "13") (pinfunction "I1_13") (pintype "input"))
      (node (ref "E8") (pin "4") (pinfunction "I1_4") (pintype "input"))
    )
    (net (code "2") (name "8{slash}~{12}") (class "Default")
      (node (ref "E10") (pin "13") (pinfunction "I2_13") (pintype "input"))
      (node (ref "E16") (pin "6") (pinfunction "~{Q}_6") (pintype "output"))
      (node (ref "E24") (pin "1") (pinfunction "I0_1") (pintype "input"))
      (node (ref "E5") (pin "2") (pinfunction "I1_2") (pintype "input"))
      (node (ref "E8") (pin "1") (pinfunction "I0_1") (pintype "input"))
      (node (ref "IC8") (pin "1") (pinfunction "I0_1") (pintype "input"))
      (node (ref "IC8") (pin "2") (pinfunction "I1_2") (pintype "input"))
    )
    (net (code "3") (name "BAC00") (class "Default")
      (node (ref "D36L1") (pin "D") (pinfunction "4_D") (pintype "passive"))
      (node (ref "D36L2") (pin "D") (pinfunction "4_D") (pintype "passive"))
      (node (ref "E23") (pin "7") (pinfunction "D_7") (pintype "input"))
    )
    (net (code "4") (name "BAC01") (class "Default")
      (node (ref "D36L1") (pin "J") (pinfunction "8_J") (pintype "passive"))
      (node (ref "D36L2") (pin "J") (pinfunction "8_J") (pintype "passive"))
      (node (ref "E23") (pin "6") (pinfunction "C_6") (pintype "input"))
    )
    (net (code "5") (name "BAC02") (class "Default")
      (node (ref "D36L1") (pin "N") (pinfunction "12_N") (pintype "passive"))
      (node (ref "D36L2") (pin "N") (pinfunction "12_N") (pintype "passive"))
      (node (ref "E23") (pin "5") (pinfunction "B_5") (pintype "input"))
    )
    (net (code "6") (name "BAC03") (class "Default")
      (node (ref "D36L1") (pin "T") (pinfunction "16_T") (pintype "passive"))
      (node (ref "D36L2") (pin "T") (pinfunction "16_T") (pintype "passive"))
      (node (ref "E23") (pin "4") (pinfunction "A_4") (pintype "input"))
    )
    (net (code "7") (name "BAC04") (class "Default")
      (node (ref "D36L1") (pin "X") (pinfunction "20_X") (pintype "passive"))
      (node (ref "D36L2") (pin "X") (pinfunction "20_X") (pintype "passive"))
      (node (ref "E16") (pin "12") (pinfunction "D_12") (pintype "input"))
      (node (ref "E21") (pin "7") (pinfunction "D_7") (pintype "input"))
    )
    (net (code "8") (name "BAC05") (class "Default")
      (node (ref "D36L1") (pin "BB") (pinfunction "24_BB") (pintype "passive"))
      (node (ref "D36L2") (pin "BB") (pinfunction "24_BB") (pintype "passive"))
      (node (ref "E16") (pin "2") (pinfunction "D_2") (pintype "input"))
      (node (ref "E21") (pin "6") (pinfunction "C_6") (pintype "input"))
    )
    (net (code "9") (name "BAC06") (class "Default")
      (node (ref "D36L1") (pin "FF") (pinfunction "28_FF") (pintype "passive"))
      (node (ref "D36L2") (pin "FF") (pinfunction "28_FF") (pintype "passive"))
      (node (ref "E21") (pin "5") (pinfunction "B_5") (pintype "input"))
    )
    (net (code "10") (name "BAC07") (class "Default")
      (node (ref "D36L1") (pin "LL") (pinfunction "32_LL") (pintype "passive"))
      (node (ref "D36L2") (pin "LL") (pinfunction "32_LL") (pintype "passive"))
      (node (ref "E21") (pin "4") (pinfunction "A_4") (pintype "input"))
    )
    (net (code "11") (name "BAC08") (class "Default")
      (node (ref "D36L1") (pin "RR") (pinfunction "36_RR") (pintype "passive"))
      (node (ref "D36L2") (pin "RR") (pinfunction "36_RR") (pintype "passive"))
      (node (ref "E22") (pin "7") (pinfunction "D_7") (pintype "input"))
    )
    (net (code "12") (name "BAC09") (class "Default")
      (node (ref "D36L1") (pin "F") (pinfunction "6_F") (pintype "passive"))
      (node (ref "D36L2") (pin "F") (pinfunction "6_F") (pintype "passive"))
      (node (ref "E22") (pin "6") (pinfunction "C_6") (pintype "input"))
    )
    (net (code "13") (name "BAC10") (class "Default")
      (node (ref "D36L1") (pin "L") (pinfunction "10_L") (pintype "passive"))
      (node (ref "D36L2") (pin "L") (pinfunction "10_L") (pintype "passive"))
      (node (ref "E22") (pin "5") (pinfunction "B_5") (pintype "input"))
    )
    (net (code "14") (name "BAC11") (class "Default")
      (node (ref "D36L1") (pin "R") (pinfunction "14_R") (pintype "passive"))
      (node (ref "D36L2") (pin "R") (pinfunction "14_R") (pintype "passive"))
      (node (ref "E22") (pin "4") (pinfunction "A_4") (pintype "input"))
      (node (ref "E30") (pin "2") (pinfunction "D_2") (pintype "input"))
    )
    (net (code "15") (name "BINIT") (class "Default")
      (node (ref "D36L1") (pin "TT") (pinfunction "38_TT") (pintype "passive"))
      (node (ref "D36L2") (pin "TT") (pinfunction "38_TT") (pintype "passive"))
      (node (ref "E1") (pin "3") (pinfunction "I0_3") (pintype "input"))
      (node (ref "LASTDEV") (pin "2") (pinfunction "2_2") (pintype "passive"))
    )
    (net (code "16") (name "BIOP1") (class "Default")
      (node (ref "D36L1") (pin "V") (pinfunction "18_V") (pintype "passive"))
      (node (ref "D36L2") (pin "V") (pinfunction "18_V") (pintype "passive"))
      (node (ref "E11") (pin "6") (pinfunction "G1_6") (pintype "input"))
      (node (ref "LASTDEV") (pin "7") (pinfunction "7_7") (pintype "passive"))
    )
    (net (code "17") (name "BIOP2") (class "Default")
      (node (ref "D36L1") (pin "Z") (pinfunction "22_Z") (pintype "passive"))
      (node (ref "D36L2") (pin "Z") (pinfunction "22_Z") (pintype "passive"))
      (node (ref "E12") (pin "6") (pinfunction "G1_6") (pintype "input"))
      (node (ref "LASTDEV") (pin "6") (pinfunction "6_6") (pintype "passive"))
    )
    (net (code "18") (name "BIOP4") (class "Default")
      (node (ref "D36L1") (pin "DD") (pinfunction "26_DD") (pintype "passive"))
      (node (ref "D36L2") (pin "DD") (pinfunction "26_DD") (pintype "passive"))
      (node (ref "E13") (pin "6") (pinfunction "G1_6") (pintype "input"))
      (node (ref "LASTDEV") (pin "5") (pinfunction "5_5") (pintype "passive"))
    )
    (net (code "19") (name "BMB00") (class "Default")
      (node (ref "D35L1") (pin "D") (pinfunction "4_D") (pintype "passive"))
      (node (ref "D35L2") (pin "D") (pinfunction "4_D") (pintype "passive"))
    )
    (net (code "20") (name "BMB01") (class "Default")
      (node (ref "D35L1") (pin "J") (pinfunction "8_J") (pintype "passive"))
      (node (ref "D35L2") (pin "J") (pinfunction "8_J") (pintype "passive"))
    )
    (net (code "21") (name "BMB02") (class "Default")
      (node (ref "D35L1") (pin "N") (pinfunction "12_N") (pintype "passive"))
      (node (ref "D35L2") (pin "N") (pinfunction "12_N") (pintype "passive"))
    )
    (net (code "22") (name "BMB03") (class "Default")
      (node (ref "D35L1") (pin "X") (pinfunction "20_X") (pintype "passive"))
      (node (ref "D35L2") (pin "X") (pinfunction "20_X") (pintype "passive"))
      (node (ref "E1") (pin "13") (pinfunction "I2_13") (pintype "input"))
    )
    (net (code "23") (name "BMB04") (class "Default")
      (node (ref "D35L1") (pin "FF") (pinfunction "28_FF") (pintype "passive"))
      (node (ref "D35L2") (pin "FF") (pinfunction "28_FF") (pintype "passive"))
      (node (ref "E1") (pin "2") (pinfunction "I1_2") (pintype "input"))
    )
    (net (code "24") (name "BMB05") (class "Default")
      (node (ref "D35L1") (pin "RR") (pinfunction "36_RR") (pintype "passive"))
      (node (ref "D35L2") (pin "RR") (pinfunction "36_RR") (pintype "passive"))
      (node (ref "E1") (pin "1") (pinfunction "I0_1") (pintype "input"))
    )
    (net (code "25") (name "BMB06") (class "Default")
      (node (ref "D35L1") (pin "L") (pinfunction "10_L") (pintype "passive"))
      (node (ref "D35L2") (pin "L") (pinfunction "10_L") (pintype "passive"))
      (node (ref "E14") (pin "3") (pinfunction "C_3") (pintype "input"))
    )
    (net (code "26") (name "BMB07") (class "Default")
      (node (ref "D35L1") (pin "V") (pinfunction "18_V") (pintype "passive"))
      (node (ref "D35L2") (pin "V") (pinfunction "18_V") (pintype "passive"))
      (node (ref "E14") (pin "2") (pinfunction "B_2") (pintype "input"))
    )
    (net (code "27") (name "BMB08") (class "Default")
      (node (ref "D35L1") (pin "DD") (pinfunction "26_DD") (pintype "passive"))
      (node (ref "D35L2") (pin "DD") (pinfunction "26_DD") (pintype "passive"))
      (node (ref "E14") (pin "1") (pinfunction "A_1") (pintype "input"))
    )
    (net (code "28") (name "BMB09") (class "Default")
      (node (ref "D35L1") (pin "JJ") (pinfunction "30_JJ") (pintype "passive"))
      (node (ref "D35L2") (pin "JJ") (pinfunction "30_JJ") (pintype "passive"))
      (node (ref "E11") (pin "3") (pinfunction "C_3") (pintype "input"))
      (node (ref "E12") (pin "3") (pinfunction "C_3") (pintype "input"))
      (node (ref "E13") (pin "3") (pinfunction "C_3") (pintype "input"))
    )
    (net (code "29") (name "BMB10") (class "Default")
      (node (ref "D35L1") (pin "NN") (pinfunction "34_NN") (pintype "passive"))
      (node (ref "D35L2") (pin "NN") (pinfunction "34_NN") (pintype "passive"))
      (node (ref "E11") (pin "2") (pinfunction "B_2") (pintype "input"))
      (node (ref "E12") (pin "2") (pinfunction "B_2") (pintype "input"))
      (node (ref "E13") (pin "2") (pinfunction "B_2") (pintype "input"))
    )
    (net (code "30") (name "BMB11") (class "Default")
      (node (ref "D35L1") (pin "TT") (pinfunction "38_TT") (pintype "passive"))
      (node (ref "D35L2") (pin "TT") (pinfunction "38_TT") (pintype "passive"))
      (node (ref "E11") (pin "1") (pinfunction "A_1") (pintype "input"))
      (node (ref "E12") (pin "1") (pinfunction "A_1") (pintype "input"))
      (node (ref "E13") (pin "1") (pinfunction "A_1") (pintype "input"))
    )
    (net (code "31") (name "BTS1") (class "Default")
      (node (ref "D36L1") (pin "NN") (pinfunction "34_NN") (pintype "passive"))
      (node (ref "D36L2") (pin "NN") (pinfunction "34_NN") (pintype "passive"))
      (node (ref "LASTDEV") (pin "3") (pinfunction "3_3") (pintype "passive"))
    )
    (net (code "32") (name "BTS3") (class "Default")
      (node (ref "D36L1") (pin "JJ") (pinfunction "30_JJ") (pintype "passive"))
      (node (ref "D36L2") (pin "JJ") (pinfunction "30_JJ") (pintype "passive"))
      (node (ref "LASTDEV") (pin "4") (pinfunction "4_4") (pintype "passive"))
    )
    (net (code "33") (name "CLK_BUF") (class "Default")
      (node (ref "E21") (pin "10") (pinfunction "CLK_10") (pintype "input"))
      (node (ref "E22") (pin "10") (pinfunction "CLK_10") (pintype "input"))
      (node (ref "E23") (pin "10") (pinfunction "CLK_10") (pintype "input"))
      (node (ref "E4") (pin "2") (pinfunction "CLK_2") (pintype "input"))
      (node (ref "E5") (pin "6") (pinfunction "O_6") (pintype "output"))
    )
    (net (code "34") (name "DONE") (class "Default")
      (node (ref "E17") (pin "4") (pinfunction "J_4") (pintype "input"))
      (node (ref "E20") (pin "13") (pinfunction "I1_13") (pintype "input"))
      (node (ref "E25") (pin "3") (pinfunction "I_3") (pintype "input"))
      (node (ref "E26") (pin "9") (pinfunction "I0_9") (pintype "input"))
      (node (ref "E31") (pin "10") (pinfunction "I1_10") (pintype "input"))
      (node (ref "E31") (pin "4") (pinfunction "I2_4") (pintype "input"))
      (node (ref "E32") (pin "11") (pinfunction "I2_11") (pintype "input"))
      (node (ref "E36") (pin "10") (pinfunction "O_10") (pintype "output"))
    )
    (net (code "35") (name "DONE_FF") (class "Default")
      (node (ref "E17") (pin "15") (pinfunction "Q_15") (pintype "output"))
      (node (ref "IC10") (pin "6") (pinfunction "I0_6") (pintype "input"))
    )
    (net (code "36") (name "DONE_SKIP") (class "Default")
      (node (ref "E17") (pin "16") (pinfunction "K_16") (pintype "input"))
      (node (ref "E18") (pin "10") (pinfunction "O_10") (pintype "output"))
      (node (ref "E20") (pin "5") (pinfunction "I1_5") (pintype "input"))
      (node (ref "E26") (pin "10") (pinfunction "I1_10") (pintype "input"))
    )
    (net (code "37") (name "ERROR") (class "Default")
      (node (ref "E19") (pin "9") (pinfunction "J_9") (pintype "input"))
      (node (ref "E26") (pin "4") (pinfunction "I0_4") (pintype "input"))
      (node (ref "E36") (pin "1") (pinfunction "O_1") (pintype "output"))
    )
    (net (code "38") (name "ERR_SKIP") (class "Default")
      (node (ref "E18") (pin "4") (pinfunction "O_4") (pintype "output"))
      (node (ref "E19") (pin "12") (pinfunction "K_12") (pintype "input"))
      (node (ref "E20") (pin "4") (pinfunction "I0_4") (pintype "input"))
      (node (ref "E26") (pin "5") (pinfunction "I1_5") (pintype "input"))
    )
    (net (code "39") (name "GND") (class "Default")
      (node (ref "C1") (pin "2") (pinfunction "2_2") (pintype "passive"))
      (node (ref "C10") (pin "2") (pinfunction "2_2") (pintype "passive"))
      (node (ref "C11") (pin "2") (pinfunction "2_2") (pintype "passive"))
      (node (ref "C12") (pin "2") (pinfunction "2_2") (pintype "passive"))
      (node (ref "C13") (pin "2") (pinfunction "2_2") (pintype "passive"))
      (node (ref "C14") (pin "2") (pinfunction "2_2") (pintype "passive"))
      (node (ref "C15") (pin "2") (pinfunction "2_2") (pintype "passive"))
      (node (ref "C16") (pin "2") (pinfunction "2_2") (pintype "passive"))
      (node (ref "C17") (pin "2") (pinfunction "2_2") (pintype "passive"))
      (node (ref "C18") (pin "2") (pinfunction "2_2") (pintype "passive"))
      (node (ref "C19") (pin "2") (pinfunction "2_2") (pintype "passive"))
      (node (ref "C2") (pin "2") (pinfunction "2_2") (pintype "passive"))
      (node (ref "C20") (pin "2") (pinfunction "2_2") (pintype "passive"))
      (node (ref "C21") (pin "2") (pinfunction "2_2") (pintype "passive"))
      (node (ref "C22") (pin "2") (pinfunction "2_2") (pintype "passive"))
      (node (ref "C23") (pin "2") (pinfunction "2_2") (pintype "passive"))
      (node (ref "C24") (pin "2") (pinfunction "2_2") (pintype "passive"))
      (node (ref "C25") (pin "2") (pinfunction "2_2") (pintype "passive"))
      (node (ref "C26") (pin "2") (pinfunction "2_2") (pintype "passive"))
      (node (ref "C27") (pin "2") (pinfunction "2_2") (pintype "passive"))
      (node (ref "C28") (pin "2") (pinfunction "2_2") (pintype "passive"))
      (node (ref "C29") (pin "2") (pinfunction "2_2") (pintype "passive"))
      (node (ref "C3") (pin "2") (pinfunction "2_2") (pintype "passive"))
      (node (ref "C30") (pin "2") (pinfunction "2_2") (pintype "passive"))
      (node (ref "C31") (pin "2") (pinfunction "2_2") (pintype "passive"))
      (node (ref "C32") (pin "2") (pinfunction "2_2") (pintype "passive"))
      (node (ref "C33") (pin "2") (pinfunction "2_2") (pintype "passive"))
      (node (ref "C34") (pin "2") (pinfunction "2_2") (pintype "passive"))
      (node (ref "C35") (pin "2") (pinfunction "2_2") (pintype "passive"))
      (node (ref "C36") (pin "2") (pinfunction "2_2") (pintype "passive"))
      (node (ref "C37") (pin "2") (pinfunction "2_2") (pintype "passive"))
      (node (ref "C38") (pin "2") (pinfunction "2_2") (pintype "passive"))
      (node (ref "C39") (pin "2") (pinfunction "2_2") (pintype "passive"))
      (node (ref "C4") (pin "2") (pinfunction "2_2") (pintype "passive"))
      (node (ref "C40") (pin "-") (pinfunction "-_-") (pintype "passive"))
      (node (ref "C5") (pin "2") (pinfunction "2_2") (pintype "passive"))
      (node (ref "C6") (pin "2") (pinfunction "2_2") (pintype "passive"))
      (node (ref "C7") (pin "2") (pinfunction "2_2") (pintype "passive"))
      (node (ref "C8") (pin "2") (pinfunction "2_2") (pintype "passive"))
      (node (ref "C9") (pin "2") (pinfunction "2_2") (pintype "passive"))
      (node (ref "D34L1") (pin "A") (pinfunction "1_A") (pintype "passive"))
      (node (ref "D34L1") (pin "AA") (pinfunction "23_AA") (pintype "passive"))
      (node (ref "D34L1") (pin "C") (pinfunction "3_C") (pintype "passive"))
      (node (ref "D34L1") (pin "CC") (pinfunction "25_CC") (pintype "passive"))
      (node (ref "D34L1") (pin "E") (pinfunction "5_E") (pintype "passive"))
      (node (ref "D34L1") (pin "EE") (pinfunction "27_EE") (pintype "passive"))
      (node (ref "D34L1") (pin "H") (pinfunction "7_H") (pintype "passive"))
      (node (ref "D34L1") (pin "HH") (pinfunction "29_HH") (pintype "passive"))
      (node (ref "D34L1") (pin "K") (pinfunction "9_K") (pintype "passive"))
      (node (ref "D34L1") (pin "KK") (pinfunction "31_KK") (pintype "passive"))
      (node (ref "D34L1") (pin "M") (pinfunction "11_M") (pintype "passive"))
      (node (ref "D34L1") (pin "MM") (pinfunction "33_MM") (pintype "passive"))
      (node (ref "D34L1") (pin "P") (pinfunction "13_P") (pintype "passive"))
      (node (ref "D34L1") (pin "PP") (pinfunction "35_PP") (pintype "passive"))
      (node (ref "D34L1") (pin "S") (pinfunction "15_S") (pintype "passive"))
      (node (ref "D34L1") (pin "SS") (pinfunction "37_SS") (pintype "passive"))
      (node (ref "D34L1") (pin "U") (pinfunction "17_U") (pintype "passive"))
      (node (ref "D34L1") (pin "UU") (pinfunction "39_UU") (pintype "passive"))
      (node (ref "D34L1") (pin "W") (pinfunction "19_W") (pintype "passive"))
      (node (ref "D34L1") (pin "Y") (pinfunction "21_Y") (pintype "passive"))
      (node (ref "D34L2") (pin "A") (pinfunction "1_A") (pintype "passive"))
      (node (ref "D34L2") (pin "AA") (pinfunction "23_AA") (pintype "passive"))
      (node (ref "D34L2") (pin "C") (pinfunction "3_C") (pintype "passive"))
      (node (ref "D34L2") (pin "CC") (pinfunction "25_CC") (pintype "passive"))
      (node (ref "D34L2") (pin "E") (pinfunction "5_E") (pintype "passive"))
      (node (ref "D34L2") (pin "EE") (pinfunction "27_EE") (pintype "passive"))
      (node (ref "D34L2") (pin "H") (pinfunction "7_H") (pintype "passive"))
      (node (ref "D34L2") (pin "HH") (pinfunction "29_HH") (pintype "passive"))
      (node (ref "D34L2") (pin "K") (pinfunction "9_K") (pintype "passive"))
      (node (ref "D34L2") (pin "KK") (pinfunction "31_KK") (pintype "passive"))
      (node (ref "D34L2") (pin "M") (pinfunction "11_M") (pintype "passive"))
      (node (ref "D34L2") (pin "MM") (pinfunction "33_MM") (pintype "passive"))
      (node (ref "D34L2") (pin "P") (pinfunction "13_P") (pintype "passive"))
      (node (ref "D34L2") (pin "PP") (pinfunction "35_PP") (pintype "passive"))
      (node (ref "D34L2") (pin "S") (pinfunction "15_S") (pintype "passive"))
      (node (ref "D34L2") (pin "SS") (pinfunction "37_SS") (pintype "passive"))
      (node (ref "D34L2") (pin "U") (pinfunction "17_U") (pintype "passive"))
      (node (ref "D34L2") (pin "UU") (pinfunction "39_UU") (pintype "passive"))
      (node (ref "D34L2") (pin "W") (pinfunction "19_W") (pintype "passive"))
      (node (ref "D34L2") (pin "Y") (pinfunction "21_Y") (pintype "passive"))
      (node (ref "D35L1") (pin "A") (pinfunction "1_A") (pintype "passive"))
      (node (ref "D35L1") (pin "AA") (pinfunction "23_AA") (pintype "passive"))
      (node (ref "D35L1") (pin "C") (pinfunction "3_C") (pintype "passive"))
      (node (ref "D35L1") (pin "CC") (pinfunction "25_CC") (pintype "passive"))
      (node (ref "D35L1") (pin "E") (pinfunction "5_E") (pintype "passive"))
      (node (ref "D35L1") (pin "EE") (pinfunction "27_EE") (pintype "passive"))
      (node (ref "D35L1") (pin "H") (pinfunction "7_H") (pintype "passive"))
      (node (ref "D35L1") (pin "HH") (pinfunction "29_HH") (pintype "passive"))
      (node (ref "D35L1") (pin "K") (pinfunction "9_K") (pintype "passive"))
      (node (ref "D35L1") (pin "KK") (pinfunction "31_KK") (pintype "passive"))
      (node (ref "D35L1") (pin "M") (pinfunction "11_M") (pintype "passive"))
      (node (ref "D35L1") (pin "MM") (pinfunction "33_MM") (pintype "passive"))
      (node (ref "D35L1") (pin "P") (pinfunction "13_P") (pintype "passive"))
      (node (ref "D35L1") (pin "PP") (pinfunction "35_PP") (pintype "passive"))
      (node (ref "D35L1") (pin "S") (pinfunction "15_S") (pintype "passive"))
      (node (ref "D35L1") (pin "SS") (pinfunction "37_SS") (pintype "passive"))
      (node (ref "D35L1") (pin "U") (pinfunction "17_U") (pintype "passive"))
      (node (ref "D35L1") (pin "UU") (pinfunction "39_UU") (pintype "passive"))
      (node (ref "D35L1") (pin "W") (pinfunction "19_W") (pintype "passive"))
      (node (ref "D35L1") (pin "Y") (pinfunction "21_Y") (pintype "passive"))
      (node (ref "D35L2") (pin "A") (pinfunction "1_A") (pintype "passive"))
      (node (ref "D35L2") (pin "AA") (pinfunction "23_AA") (pintype "passive"))
      (node (ref "D35L2") (pin "C") (pinfunction "3_C") (pintype "passive"))
      (node (ref "D35L2") (pin "CC") (pinfunction "25_CC") (pintype "passive"))
      (node (ref "D35L2") (pin "E") (pinfunction "5_E") (pintype "passive"))
      (node (ref "D35L2") (pin "EE") (pinfunction "27_EE") (pintype "passive"))
      (node (ref "D35L2") (pin "H") (pinfunction "7_H") (pintype "passive"))
      (node (ref "D35L2") (pin "HH") (pinfunction "29_HH") (pintype "passive"))
      (node (ref "D35L2") (pin "K") (pinfunction "9_K") (pintype "passive"))
      (node (ref "D35L2") (pin "KK") (pinfunction "31_KK") (pintype "passive"))
      (node (ref "D35L2") (pin "M") (pinfunction "11_M") (pintype "passive"))
      (node (ref "D35L2") (pin "MM") (pinfunction "33_MM") (pintype "passive"))
      (node (ref "D35L2") (pin "P") (pinfunction "13_P") (pintype "passive"))
      (node (ref "D35L2") (pin "PP") (pinfunction "35_PP") (pintype "passive"))
      (node (ref "D35L2") (pin "S") (pinfunction "15_S") (pintype "passive"))
      (node (ref "D35L2") (pin "SS") (pinfunction "37_SS") (pintype "passive"))
      (node (ref "D35L2") (pin "U") (pinfunction "17_U") (pintype "passive"))
      (node (ref "D35L2") (pin "UU") (pinfunction "39_UU") (pintype "passive"))
      (node (ref "D35L2") (pin "W") (pinfunction "19_W") (pintype "passive"))
      (node (ref "D35L2") (pin "Y") (pinfunction "21_Y") (pintype "passive"))
      (node (ref "D36L1") (pin "A") (pinfunction "1_A") (pintype "passive"))
      (node (ref "D36L1") (pin "AA") (pinfunction "23_AA") (pintype "passive"))
      (node (ref "D36L1") (pin "C") (pinfunction "3_C") (pintype "passive"))
      (node (ref "D36L1") (pin "CC") (pinfunction "25_CC") (pintype "passive"))
      (node (ref "D36L1") (pin "E") (pinfunction "5_E") (pintype "passive"))
      (node (ref "D36L1") (pin "EE") (pinfunction "27_EE") (pintype "passive"))
      (node (ref "D36L1") (pin "H") (pinfunction "7_H") (pintype "passive"))
      (node (ref "D36L1") (pin "HH") (pinfunction "29_HH") (pintype "passive"))
      (node (ref "D36L1") (pin "K") (pinfunction "9_K") (pintype "passive"))
      (node (ref "D36L1") (pin "KK") (pinfunction "31_KK") (pintype "passive"))
      (node (ref "D36L1") (pin "M") (pinfunction "11_M") (pintype "passive"))
      (node (ref "D36L1") (pin "MM") (pinfunction "33_MM") (pintype "passive"))
      (node (ref "D36L1") (pin "P") (pinfunction "13_P") (pintype "passive"))
      (node (ref "D36L1") (pin "PP") (pinfunction "35_PP") (pintype "passive"))
      (node (ref "D36L1") (pin "S") (pinfunction "15_S") (pintype "passive"))
      (node (ref "D36L1") (pin "SS") (pinfunction "37_SS") (pintype "passive"))
      (node (ref "D36L1") (pin "U") (pinfunction "17_U") (pintype "passive"))
      (node (ref "D36L1") (pin "UU") (pinfunction "39_UU") (pintype "passive"))
      (node (ref "D36L1") (pin "W") (pinfunction "19_W") (pintype "passive"))
      (node (ref "D36L1") (pin "Y") (pinfunction "21_Y") (pintype "passive"))
      (node (ref "D36L2") (pin "A") (pinfunction "1_A") (pintype "passive"))
      (node (ref "D36L2") (pin "AA") (pinfunction "23_AA") (pintype "passive"))
      (node (ref "D36L2") (pin "C") (pinfunction "3_C") (pintype "passive"))
      (node (ref "D36L2") (pin "CC") (pinfunction "25_CC") (pintype "passive"))
      (node (ref "D36L2") (pin "E") (pinfunction "5_E") (pintype "passive"))
      (node (ref "D36L2") (pin "EE") (pinfunction "27_EE") (pintype "passive"))
      (node (ref "D36L2") (pin "H") (pinfunction "7_H") (pintype "passive"))
      (node (ref "D36L2") (pin "HH") (pinfunction "29_HH") (pintype "passive"))
      (node (ref "D36L2") (pin "K") (pinfunction "9_K") (pintype "passive"))
      (node (ref "D36L2") (pin "KK") (pinfunction "31_KK") (pintype "passive"))
      (node (ref "D36L2") (pin "M") (pinfunction "11_M") (pintype "passive"))
      (node (ref "D36L2") (pin "MM") (pinfunction "33_MM") (pintype "passive"))
      (node (ref "D36L2") (pin "P") (pinfunction "13_P") (pintype "passive"))
      (node (ref "D36L2") (pin "PP") (pinfunction "35_PP") (pintype "passive"))
      (node (ref "D36L2") (pin "S") (pinfunction "15_S") (pintype "passive"))
      (node (ref "D36L2") (pin "SS") (pinfunction "37_SS") (pintype "passive"))
      (node (ref "D36L2") (pin "U") (pinfunction "17_U") (pintype "passive"))
      (node (ref "D36L2") (pin "UU") (pinfunction "39_UU") (pintype "passive"))
      (node (ref "D36L2") (pin "W") (pinfunction "19_W") (pintype "passive"))
      (node (ref "D36L2") (pin "Y") (pinfunction "21_Y") (pintype "passive"))
      (node (ref "DRIVE") (pin "A") (pinfunction "1_A") (pintype "passive"))
      (node (ref "DRIVE") (pin "AA") (pinfunction "23_AA") (pintype "passive"))
      (node (ref "DRIVE") (pin "B") (pinfunction "2_B") (pintype "passive"))
      (node (ref "DRIVE") (pin "C") (pinfunction "3_C") (pintype "passive"))
      (node (ref "DRIVE") (pin "CC") (pinfunction "25_CC") (pintype "passive"))
      (node (ref "DRIVE") (pin "DD") (pinfunction "26_DD") (pintype "passive"))
      (node (ref "DRIVE") (pin "E") (pinfunction "5_E") (pintype "passive"))
      (node (ref "DRIVE") (pin "EE") (pinfunction "27_EE") (pintype "passive"))
      (node (ref "DRIVE") (pin "F") (pinfunction "6_F") (pintype "passive"))
      (node (ref "DRIVE") (pin "H") (pinfunction "7_H") (pintype "passive"))
      (node (ref "DRIVE") (pin "HH") (pinfunction "29_HH") (pintype "passive"))
      (node (ref "DRIVE") (pin "JJ") (pinfunction "30_JJ") (pintype "passive"))
      (node (ref "DRIVE") (pin "K") (pinfunction "9_K") (pintype "passive"))
      (node (ref "DRIVE") (pin "KK") (pinfunction "31_KK") (pintype "passive"))
      (node (ref "DRIVE") (pin "L") (pinfunction "10_L") (pintype "passive"))
      (node (ref "DRIVE") (pin "M") (pinfunction "11_M") (pintype "passive"))
      (node (ref "DRIVE") (pin "MM") (pinfunction "33_MM") (pintype "passive"))
      (node (ref "DRIVE") (pin "NN") (pinfunction "34_NN") (pintype "passive"))
      (node (ref "DRIVE") (pin "P") (pinfunction "13_P") (pintype "passive"))
      (node (ref "DRIVE") (pin "PP") (pinfunction "35_PP") (pintype "passive"))
      (node (ref "DRIVE") (pin "R") (pinfunction "14_R") (pintype "passive"))
      (node (ref "DRIVE") (pin "S") (pinfunction "15_S") (pintype "passive"))
      (node (ref "DRIVE") (pin "SS") (pinfunction "37_SS") (pintype "passive"))
      (node (ref "DRIVE") (pin "TT") (pinfunction "38_TT") (pintype "passive"))
      (node (ref "DRIVE") (pin "U") (pinfunction "17_U") (pintype "passive"))
      (node (ref "DRIVE") (pin "UU") (pinfunction "39_UU") (pintype "passive"))
      (node (ref "DRIVE") (pin "V") (pinfunction "18_V") (pintype "passive"))
      (node (ref "DRIVE") (pin "VV") (pinfunction "40_VV") (pintype "passive"))
      (node (ref "DRIVE") (pin "W") (pinfunction "19_W") (pintype "passive"))
      (node (ref "DRIVE") (pin "Y") (pinfunction "21_Y") (pintype "passive"))
      (node (ref "DRIVE") (pin "Z") (pinfunction "22_Z") (pintype "passive"))
      (node (ref "E1") (pin "4") (pinfunction "I1_4") (pintype "input"))
      (node (ref "E1") (pin "5") (pinfunction "I2_5") (pintype "input"))
      (node (ref "E11") (pin "5") (pinfunction "G2B_5") (pintype "input"))
      (node (ref "E12") (pin "5") (pinfunction "G2B_5") (pintype "input"))
      (node (ref "E13") (pin "5") (pinfunction "G2B_5") (pintype "input"))
      (node (ref "E2") (pin "2") (pinfunction "D_2") (pintype "input"))
      (node (ref "E4") (pin "6") (pinfunction "D_6") (pintype "input"))
      (node (ref "LASTDEV") (pin "1") (pinfunction "1_1") (pintype "passive"))
      (node (ref "R10") (pin "1") (pinfunction "1_1") (pintype "passive"))
      (node (ref "R11") (pin "1") (pinfunction "1_1") (pintype "passive"))
      (node (ref "R12") (pin "1") (pinfunction "1_1") (pintype "passive"))
      (node (ref "R13") (pin "1") (pinfunction "1_1") (pintype "passive"))
      (node (ref "R14") (pin "1") (pinfunction "1_1") (pintype "passive"))
      (node (ref "R15") (pin "1") (pinfunction "1_1") (pintype "passive"))
      (node (ref "R16") (pin "1") (pinfunction "1_1") (pintype "passive"))
      (node (ref "R17") (pin "1") (pinfunction "1_1") (pintype "passive"))
      (node (ref "SL1") (pin "2") (pinfunction "S_2") (pintype "passive"))
      (node (ref "SL1") (pin "3") (pinfunction "S_3") (pintype "passive"))
    )
    (net (code "40") (name "INIT") (class "Default")
      (node (ref "E1") (pin "8") (pinfunction "O_8") (pintype "output"))
      (node (ref "E15") (pin "4") (pinfunction "I0_4") (pintype "input"))
      (node (ref "E15") (pin "5") (pinfunction "I1_5") (pintype "input"))
      (node (ref "E18") (pin "12") (pinfunction "I1_12") (pintype "input"))
      (node (ref "IC8") (pin "6") (pinfunction "I0_6") (pintype "input"))
      (node (ref "IC8") (pin "7") (pinfunction "I1_7") (pintype "input"))
    )
    (net (code "41") (name "MAINT") (class "Default")
      (node (ref "E16") (pin "9") (pinfunction "Q_9") (pintype "output"))
      (node (ref "E32") (pin "9") (pinfunction "I0_9") (pintype "input"))
      (node (ref "E35") (pin "3") (pinfunction "I1_3") (pintype "input"))
      (node (ref "E35") (pin "6") (pinfunction "I1_6") (pintype "input"))
      (node (ref "E35") (pin "9") (pinfunction "I1_9") (pintype "input"))
      (node (ref "E36") (pin "2") (pinfunction "I0_2") (pintype "input"))
      (node (ref "E36") (pin "6") (pinfunction "I1_6") (pintype "input"))
      (node (ref "E36") (pin "9") (pinfunction "I1_9") (pintype "input"))
    )
    (net (code "42") (name "MSB8") (class "Default")
      (node (ref "E21") (pin "12") (pinfunction "QD_12") (pintype "output"))
      (node (ref "E23") (pin "2") (pinfunction "J_2") (pintype "input"))
      (node (ref "E23") (pin "3") (pinfunction "K_3") (pintype "input"))
      (node (ref "E8") (pin "5") (pinfunction "I2_5") (pintype "input"))
      (node (ref "IC1") (pin "6") (pinfunction "I0_6") (pintype "input"))
    )
    (net (code "43") (name "MSB12") (class "Default")
      (node (ref "E23") (pin "12") (pinfunction "QD_12") (pintype "output"))
      (node (ref "E8") (pin "2") (pinfunction "I1_2") (pintype "input"))
      (node (ref "IC6") (pin "1") (pinfunction "I0_1") (pintype "input"))
    )
    (net (code "44") (name "Net-(70-P)") (class "Default")
      (node (ref "70") (pin "1") (pinfunction "P_1") (pintype "passive"))
      (node (ref "E14") (pin "15") (pinfunction "Y0_15") (pintype "output"))
    )
    (net (code "45") (name "Net-(71-P)") (class "Default")
      (node (ref "71") (pin "1") (pinfunction "P_1") (pintype "passive"))
      (node (ref "E14") (pin "14") (pinfunction "Y1_14") (pintype "output"))
    )
    (net (code "46") (name "Net-(72-P)") (class "Default")
      (node (ref "72") (pin "1") (pinfunction "P_1") (pintype "passive"))
      (node (ref "E14") (pin "13") (pinfunction "Y2_13") (pintype "output"))
    )
    (net (code "47") (name "Net-(73-P)") (class "Default")
      (node (ref "73") (pin "1") (pinfunction "P_1") (pintype "passive"))
      (node (ref "E14") (pin "12") (pinfunction "Y3_12") (pintype "output"))
    )
    (net (code "48") (name "Net-(74-P)") (class "Default")
      (node (ref "74") (pin "1") (pinfunction "P_1") (pintype "passive"))
      (node (ref "E14") (pin "11") (pinfunction "Y4_11") (pintype "output"))
    )
    (net (code "49") (name "Net-(75-P)") (class "Default")
      (node (ref "75") (pin "1") (pinfunction "P_1") (pintype "passive"))
      (node (ref "E14") (pin "10") (pinfunction "Y5_10") (pintype "output"))
    )
    (net (code "50") (name "Net-(76-P)") (class "Default")
      (node (ref "76") (pin "1") (pinfunction "P_1") (pintype "passive"))
      (node (ref "E14") (pin "9") (pinfunction "Y6_9") (pintype "output"))
    )
    (net (code "51") (name "Net-(77-P)") (class "Default")
      (node (ref "77") (pin "1") (pinfunction "P_1") (pintype "passive"))
      (node (ref "E14") (pin "7") (pinfunction "Y7_7") (pintype "output"))
    )
    (net (code "52") (name "Net-(E1B-O)") (class "Default")
      (node (ref "E1") (pin "10") (pinfunction "I1_10") (pintype "input"))
      (node (ref "E1") (pin "6") (pinfunction "O_6") (pintype "output"))
      (node (ref "E1") (pin "9") (pinfunction "I0_9") (pintype "input"))
    )
    (net (code "53") (name "Net-(E1C-I2)") (class "Default")
      (node (ref "E1") (pin "11") (pinfunction "I2_11") (pintype "input"))
      (node (ref "E2") (pin "6") (pinfunction "~{Q}_6") (pintype "output"))
    )
    (net (code "54") (name "Net-(E4A-A)") (class "Default")
      (node (ref "E4") (pin "10") (pinfunction "ENT_10") (pintype "input"))
      (node (ref "E4") (pin "3") (pinfunction "A_3") (pintype "input"))
      (node (ref "E4") (pin "4") (pinfunction "B_4") (pintype "input"))
      (node (ref "E4") (pin "7") (pinfunction "ENP_7") (pintype "input"))
      (node (ref "R19") (pin "2") (pinfunction "2_2") (pintype "passive"))
    )
    (net (code "55") (name "Net-(E4A-C)") (class "Default")
      (node (ref "E4") (pin "5") (pinfunction "C_5") (pintype "input"))
      (node (ref "E5") (pin "3") (pinfunction "O_3") (pintype "output"))
    )
    (net (code "56") (name "Net-(E5A-I0)") (class "Default")
      (node (ref "E5") (pin "1") (pinfunction "I0_1") (pintype "input"))
      (node (ref "E5") (pin "11") (pinfunction "O_11") (pintype "output"))
    )
    (net (code "57") (name "Net-(E8A-O)") (class "Default")
      (node (ref "E8") (pin "11") (pinfunction "I2_11") (pintype "input"))
      (node (ref "E8") (pin "12") (pinfunction "O_12") (pintype "output"))
    )
    (net (code "58") (name "Net-(E8B-O)") (class "Default")
      (node (ref "E8") (pin "6") (pinfunction "O_6") (pintype "output"))
      (node (ref "E8") (pin "9") (pinfunction "I0_9") (pintype "input"))
    )
    (net (code "59") (name "Net-(E10A-I0)") (class "Default")
      (node (ref "E10") (pin "1") (pinfunction "I0_1") (pintype "input"))
      (node (ref "E10") (pin "6") (pinfunction "O_6") (pintype "output"))
    )
    (net (code "60") (name "Net-(E10A-O)") (class "Default")
      (node (ref "E10") (pin "10") (pinfunction "I1_10") (pintype "input"))
      (node (ref "E10") (pin "11") (pinfunction "I2_11") (pintype "input"))
      (node (ref "E10") (pin "12") (pinfunction "O_12") (pintype "output"))
    )
    (net (code "61") (name "Net-(E10C-O)") (class "Default")
      (node (ref "E10") (pin "8") (pinfunction "O_8") (pintype "output"))
      (node (ref "IC7") (pin "1") (pinfunction "I0_1") (pintype "input"))
      (node (ref "IC7") (pin "2") (pinfunction "I1_2") (pintype "input"))
    )
    (net (code "62") (name "Net-(E14A-G2A)") (class "Default")
      (node (ref "E1") (pin "12") (pinfunction "O_12") (pintype "output"))
      (node (ref "E14") (pin "4") (pinfunction "G2A_4") (pintype "input"))
      (node (ref "E14") (pin "5") (pinfunction "G2B_5") (pintype "input"))
    )
    (net (code "63") (name "Net-(E15A-O)") (class "Default")
      (node (ref "E15") (pin "3") (pinfunction "O_3") (pintype "output"))
      (node (ref "E8") (pin "13") (pinfunction "I2_13") (pintype "input"))
      (node (ref "E8") (pin "3") (pinfunction "I0_3") (pintype "input"))
    )
    (net (code "64") (name "Net-(E15C-I0)") (class "Default")
      (node (ref "E15") (pin "9") (pinfunction "I0_9") (pintype "input"))
      (node (ref "E20") (pin "11") (pinfunction "O_11") (pintype "output"))
      (node (ref "E24") (pin "10") (pinfunction "I1_10") (pintype "input"))
    )
    (net (code "65") (name "Net-(E15C-O)") (class "Default")
      (node (ref "E15") (pin "8") (pinfunction "O_8") (pintype "output"))
      (node (ref "E24") (pin "12") (pinfunction "I0_12") (pintype "input"))
    )
    (net (code "66") (name "Net-(E15D-O)") (class "Default")
      (node (ref "E15") (pin "11") (pinfunction "O_11") (pintype "output"))
      (node (ref "E8") (pin "10") (pinfunction "I1_10") (pintype "input"))
    )
    (net (code "67") (name "Net-(E17A-CLK)") (class "Default")
      (node (ref "E17") (pin "1") (pinfunction "CLK_1") (pintype "input"))
      (node (ref "E26") (pin "8") (pinfunction "O_8") (pintype "output"))
    )
    (net (code "68") (name "Net-(E17A-~{Q})") (class "Default")
      (node (ref "E17") (pin "14") (pinfunction "~{Q}_14") (pintype "output"))
      (node (ref "E18") (pin "9") (pinfunction "I1_9") (pintype "input"))
    )
    (net (code "69") (name "Net-(E17B-CLR)") (class "Default")
      (node (ref "E17") (pin "8") (pinfunction "CLR_8") (pintype "input"))
      (node (ref "E18") (pin "13") (pinfunction "O_13") (pintype "output"))
    )
    (net (code "70") (name "Net-(E17B-J)") (class "Default")
      (node (ref "E17") (pin "12") (pinfunction "K_12") (pintype "input"))
      (node (ref "E17") (pin "9") (pinfunction "J_9") (pintype "input"))
      (node (ref "E8") (pin "8") (pinfunction "O_8") (pintype "output"))
      (node (ref "IC7") (pin "7") (pinfunction "I1_7") (pintype "input"))
    )
    (net (code "71") (name "Net-(E18A-I1)") (class "Default")
      (node (ref "E18") (pin "3") (pinfunction "I1_3") (pintype "input"))
      (node (ref "E19") (pin "14") (pinfunction "~{Q}_14") (pintype "output"))
    )
    (net (code "72") (name "Net-(E18B-I1)") (class "Default")
      (node (ref "E18") (pin "6") (pinfunction "I1_6") (pintype "input"))
      (node (ref "E19") (pin "10") (pinfunction "~{Q}_10") (pintype "output"))
    )
    (net (code "73") (name "Net-(E19A-CLK)") (class "Default")
      (node (ref "E19") (pin "1") (pinfunction "CLK_1") (pintype "input"))
      (node (ref "E26") (pin "3") (pinfunction "O_3") (pintype "output"))
    )
    (net (code "74") (name "Net-(E19B-CLK)") (class "Default")
      (node (ref "E19") (pin "6") (pinfunction "CLK_6") (pintype "input"))
      (node (ref "E26") (pin "6") (pinfunction "O_6") (pintype "output"))
    )
    (net (code "75") (name "Net-(E20A-I1)") (class "Default")
      (node (ref "E20") (pin "2") (pinfunction "I1_2") (pintype "input"))
      (node (ref "E20") (pin "6") (pinfunction "O_6") (pintype "output"))
    )
    (net (code "76") (name "Net-(E20A-O)") (class "Default")
      (node (ref "E20") (pin "3") (pinfunction "O_3") (pintype "output"))
      (node (ref "IC10") (pin "1") (pinfunction "I0_1") (pintype "input"))
      (node (ref "IC10") (pin "2") (pinfunction "I1_2") (pintype "input"))
    )
    (net (code "77") (name "Net-(E21A-J)") (class "Default")
      (node (ref "E21") (pin "2") (pinfunction "J_2") (pintype "input"))
      (node (ref "E21") (pin "3") (pinfunction "K_3") (pintype "input"))
      (node (ref "E22") (pin "12") (pinfunction "QD_12") (pintype "output"))
      (node (ref "IC4") (pin "6") (pinfunction "I0_6") (pintype "input"))
    )
    (net (code "78") (name "Net-(E21A-QA)") (class "Default")
      (node (ref "E21") (pin "15") (pinfunction "QA_15") (pintype "output"))
      (node (ref "IC3") (pin "6") (pinfunction "I0_6") (pintype "input"))
    )
    (net (code "79") (name "Net-(E21A-QB)") (class "Default")
      (node (ref "E21") (pin "14") (pinfunction "QB_14") (pintype "output"))
      (node (ref "IC3") (pin "1") (pinfunction "I0_1") (pintype "input"))
    )
    (net (code "80") (name "Net-(E21A-QC)") (class "Default")
      (node (ref "E21") (pin "13") (pinfunction "QC_13") (pintype "output"))
      (node (ref "IC4") (pin "1") (pinfunction "I0_1") (pintype "input"))
    )
    (net (code "81") (name "Net-(E22A-QA)") (class "Default")
      (node (ref "E22") (pin "15") (pinfunction "QA_15") (pintype "output"))
      (node (ref "IC2") (pin "1") (pinfunction "I0_1") (pintype "input"))
    )
    (net (code "82") (name "Net-(E22A-QB)") (class "Default")
      (node (ref "E22") (pin "14") (pinfunction "QB_14") (pintype "output"))
      (node (ref "IC5") (pin "6") (pinfunction "I0_6") (pintype "input"))
    )
    (net (code "83") (name "Net-(E22A-QC)") (class "Default")
      (node (ref "E22") (pin "13") (pinfunction "QC_13") (pintype "output"))
      (node (ref "IC5") (pin "1") (pinfunction "I0_1") (pintype "input"))
    )
    (net (code "84") (name "Net-(E23A-QA)") (class "Default")
      (node (ref "E23") (pin "15") (pinfunction "QA_15") (pintype "output"))
      (node (ref "IC2") (pin "6") (pinfunction "I0_6") (pintype "input"))
    )
    (net (code "85") (name "Net-(E23A-QB)") (class "Default")
      (node (ref "E23") (pin "14") (pinfunction "QB_14") (pintype "output"))
      (node (ref "IC1") (pin "1") (pinfunction "I0_1") (pintype "input"))
    )
    (net (code "86") (name "Net-(E23A-QC)") (class "Default")
      (node (ref "E23") (pin "13") (pinfunction "QC_13") (pintype "output"))
      (node (ref "IC6") (pin "6") (pinfunction "I0_6") (pintype "input"))
    )
    (net (code "87") (name "Net-(E24A-I1)") (class "Default")
      (node (ref "E24") (pin "2") (pinfunction "I1_2") (pintype "input"))
      (node (ref "E35") (pin "13") (pinfunction "O_13") (pintype "output"))
      (node (ref "IC1") (pin "7") (pinfunction "I1_7") (pintype "input"))
      (node (ref "IC2") (pin "2") (pinfunction "I1_2") (pintype "input"))
      (node (ref "IC3") (pin "2") (pinfunction "I1_2") (pintype "input"))
      (node (ref "IC3") (pin "7") (pinfunction "I1_7") (pintype "input"))
      (node (ref "IC4") (pin "2") (pinfunction "I1_2") (pintype "input"))
      (node (ref "IC4") (pin "7") (pinfunction "I1_7") (pintype "input"))
      (node (ref "IC5") (pin "2") (pinfunction "I1_2") (pintype "input"))
      (node (ref "IC5") (pin "7") (pinfunction "I1_7") (pintype "input"))
    )
    (net (code "88") (name "Net-(E24A-O)") (class "Default")
      (node (ref "E24") (pin "3") (pinfunction "O_3") (pintype "output"))
      (node (ref "IC1") (pin "2") (pinfunction "I1_2") (pintype "input"))
      (node (ref "IC2") (pin "7") (pinfunction "I1_7") (pintype "input"))
      (node (ref "IC6") (pin "2") (pinfunction "I1_2") (pintype "input"))
      (node (ref "IC6") (pin "7") (pinfunction "I1_7") (pintype "input"))
    )
    (net (code "89") (name "Net-(E24B-O)") (class "Default")
      (node (ref "E24") (pin "6") (pinfunction "O_6") (pintype "output"))
      (node (ref "E32") (pin "1") (pinfunction "I0_1") (pintype "input"))
    )
    (net (code "90") (name "Net-(E24C-O)") (class "Default")
      (node (ref "E24") (pin "8") (pinfunction "O_8") (pintype "output"))
      (node (ref "E30") (pin "13") (pinfunction "CLR_13") (pintype "input"))
    )
    (net (code "91") (name "Net-(E25C-O)") (class "Default")
      (node (ref "E25") (pin "6") (pinfunction "O_6") (pintype "output"))
      (node (ref "E31") (pin "1") (pinfunction "I0_1") (pintype "input"))
      (node (ref "E31") (pin "2") (pinfunction "I1_2") (pintype "input"))
    )
    (net (code "92") (name "Net-(E25D-O)") (class "Default")
      (node (ref "E25") (pin "8") (pinfunction "O_8") (pintype "output"))
      (node (ref "E31") (pin "13") (pinfunction "I3_13") (pintype "input"))
    )
    (net (code "93") (name "Net-(E25E-O)") (class "Default")
      (node (ref "E25") (pin "10") (pinfunction "O_10") (pintype "output"))
      (node (ref "E26") (pin "12") (pinfunction "I0_12") (pintype "input"))
      (node (ref "E26") (pin "13") (pinfunction "I1_13") (pintype "input"))
    )
    (net (code "94") (name "Net-(E25F-O)") (class "Default")
      (node (ref "E25") (pin "12") (pinfunction "O_12") (pintype "output"))
      (node (ref "E36") (pin "11") (pinfunction "I0_11") (pintype "input"))
      (node (ref "E36") (pin "12") (pinfunction "I1_12") (pintype "input"))
    )
    (net (code "95") (name "Net-(E30A-Q)") (class "Default")
      (node (ref "E30") (pin "5") (pinfunction "Q_5") (pintype "output"))
      (node (ref "IC10") (pin "7") (pinfunction "I1_7") (pintype "input"))
    )
    (net (code "96") (name "Net-(E30B-CLK)") (class "Default")
      (node (ref "E30") (pin "11") (pinfunction "CLK_11") (pintype "input"))
      (node (ref "IC9") (pin "3") (pinfunction "O_3") (pintype "open_collector"))
      (node (ref "R18") (pin "1") (pinfunction "1_1") (pintype "passive"))
    )
    (net (code "97") (name "Net-(E31A-O)") (class "Default")
      (node (ref "E31") (pin "6") (pinfunction "O_6") (pintype "output"))
      (node (ref "IC9") (pin "1") (pinfunction "I0_1") (pintype "input"))
    )
    (net (code "98") (name "Net-(E31B-O)") (class "Default")
      (node (ref "E31") (pin "8") (pinfunction "O_8") (pintype "output"))
      (node (ref "IC9") (pin "2") (pinfunction "I1_2") (pintype "input"))
    )
    (net (code "99") (name "Net-(E32A-O)") (class "Default")
      (node (ref "E32") (pin "12") (pinfunction "O_12") (pintype "output"))
      (node (ref "E32") (pin "4") (pinfunction "I1_4") (pintype "input"))
      (node (ref "E32") (pin "5") (pinfunction "I2_5") (pintype "input"))
    )
    (net (code "100") (name "Net-(E32C-O)") (class "Default")
      (node (ref "E32") (pin "8") (pinfunction "O_8") (pintype "output"))
      (node (ref "E35") (pin "11") (pinfunction "I0_11") (pintype "input"))
    )
    (net (code "101") (name "Net-(PAD10-P)") (class "Default")
      (node (ref "E38") (pin "1") (pinfunction "1_1") (pintype "passive"))
      (node (ref "PAD10") (pin "1") (pinfunction "P_1") (pintype "passive"))
    )
    (net (code "102") (name "Net-(PAD11-P)") (class "Default")
      (node (ref "E38") (pin "2") (pinfunction "2_2") (pintype "passive"))
      (node (ref "PAD11") (pin "1") (pinfunction "P_1") (pintype "passive"))
    )
    (net (code "103") (name "Net-(PAD12-P)") (class "Default")
      (node (ref "E38") (pin "3") (pinfunction "3_3") (pintype "passive"))
      (node (ref "PAD12") (pin "1") (pinfunction "P_1") (pintype "passive"))
    )
    (net (code "104") (name "Net-(PAD13-P)") (class "Default")
      (node (ref "E38") (pin "4") (pinfunction "4_4") (pintype "passive"))
      (node (ref "PAD13") (pin "1") (pinfunction "P_1") (pintype "passive"))
    )
    (net (code "105") (name "Net-(PAD14-P)") (class "Default")
      (node (ref "E38") (pin "5") (pinfunction "5_5") (pintype "passive"))
      (node (ref "PAD14") (pin "1") (pinfunction "P_1") (pintype "passive"))
    )
    (net (code "106") (name "Net-(PAD15-P)") (class "Default")
      (node (ref "E38") (pin "6") (pinfunction "6_6") (pintype "passive"))
      (node (ref "PAD15") (pin "1") (pinfunction "P_1") (pintype "passive"))
    )
    (net (code "107") (name "Net-(PAD16-P)") (class "Default")
      (node (ref "E38") (pin "7") (pinfunction "7_7") (pintype "passive"))
      (node (ref "PAD16") (pin "1") (pinfunction "P_1") (pintype "passive"))
    )
    (net (code "108") (name "Net-(PAD17-P)") (class "Default")
      (node (ref "E38") (pin "8") (pinfunction "8_8") (pintype "passive"))
      (node (ref "PAD17") (pin "1") (pinfunction "P_1") (pintype "passive"))
    )
    (net (code "109") (name "Net-(PAD18-P)") (class "Default")
      (node (ref "E40") (pin "1") (pinfunction "1_1") (pintype "passive"))
      (node (ref "PAD18") (pin "1") (pinfunction "P_1") (pintype "passive"))
    )
    (net (code "110") (name "Net-(PAD19-P)") (class "Default")
      (node (ref "E40") (pin "2") (pinfunction "2_2") (pintype "passive"))
      (node (ref "PAD19") (pin "1") (pinfunction "P_1") (pintype "passive"))
    )
    (net (code "111") (name "Net-(PAD20-P)") (class "Default")
      (node (ref "E38") (pin "16") (pinfunction "16_16") (pintype "passive"))
      (node (ref "PAD20") (pin "1") (pinfunction "P_1") (pintype "passive"))
    )
    (net (code "112") (name "Net-(PAD21-P)") (class "Default")
      (node (ref "E38") (pin "15") (pinfunction "15_15") (pintype "passive"))
      (node (ref "PAD21") (pin "1") (pinfunction "P_1") (pintype "passive"))
    )
    (net (code "113") (name "Net-(PAD22-P)") (class "Default")
      (node (ref "E38") (pin "14") (pinfunction "14_14") (pintype "passive"))
      (node (ref "PAD22") (pin "1") (pinfunction "P_1") (pintype "passive"))
    )
    (net (code "114") (name "Net-(PAD23-P)") (class "Default")
      (node (ref "E38") (pin "13") (pinfunction "13_13") (pintype "passive"))
      (node (ref "PAD23") (pin "1") (pinfunction "P_1") (pintype "passive"))
    )
    (net (code "115") (name "Net-(PAD24-P)") (class "Default")
      (node (ref "E38") (pin "12") (pinfunction "12_12") (pintype "passive"))
      (node (ref "PAD24") (pin "1") (pinfunction "P_1") (pintype "passive"))
    )
    (net (code "116") (name "Net-(PAD25-P)") (class "Default")
      (node (ref "E38") (pin "11") (pinfunction "11_11") (pintype "passive"))
      (node (ref "PAD25") (pin "1") (pinfunction "P_1") (pintype "passive"))
    )
    (net (code "117") (name "Net-(PAD26-P)") (class "Default")
      (node (ref "E38") (pin "10") (pinfunction "10_10") (pintype "passive"))
      (node (ref "PAD26") (pin "1") (pinfunction "P_1") (pintype "passive"))
    )
    (net (code "118") (name "Net-(PAD27-P)") (class "Default")
      (node (ref "E38") (pin "9") (pinfunction "9_9") (pintype "passive"))
      (node (ref "PAD27") (pin "1") (pinfunction "P_1") (pintype "passive"))
    )
    (net (code "119") (name "Net-(PAD28-P)") (class "Default")
      (node (ref "E40") (pin "3") (pinfunction "3_3") (pintype "passive"))
      (node (ref "PAD28") (pin "1") (pinfunction "P_1") (pintype "passive"))
    )
    (net (code "120") (name "Net-(PAD29-P)") (class "Default")
      (node (ref "E40") (pin "4") (pinfunction "4_4") (pintype "passive"))
      (node (ref "PAD29") (pin "1") (pinfunction "P_1") (pintype "passive"))
    )
    (net (code "121") (name "Net-(PAD30-P)") (class "Default")
      (node (ref "E40") (pin "5") (pinfunction "5_5") (pintype "passive"))
      (node (ref "PAD30") (pin "1") (pinfunction "P_1") (pintype "passive"))
    )
    (net (code "122") (name "Net-(PAD31-P)") (class "Default")
      (node (ref "E40") (pin "6") (pinfunction "6_6") (pintype "passive"))
      (node (ref "PAD31") (pin "1") (pinfunction "P_1") (pintype "passive"))
    )
    (net (code "123") (name "Net-(PAD32-P)") (class "Default")
      (node (ref "E40") (pin "7") (pinfunction "7_7") (pintype "passive"))
      (node (ref "PAD32") (pin "1") (pinfunction "P_1") (pintype "passive"))
    )
    (net (code "124") (name "Net-(PAD33-P)") (class "Default")
      (node (ref "E40") (pin "8") (pinfunction "8_8") (pintype "passive"))
      (node (ref "PAD33") (pin "1") (pinfunction "P_1") (pintype "passive"))
    )
    (net (code "125") (name "Net-(PAD34-P)") (class "Default")
      (node (ref "E40") (pin "16") (pinfunction "16_16") (pintype "passive"))
      (node (ref "PAD34") (pin "1") (pinfunction "P_1") (pintype "passive"))
    )
    (net (code "126") (name "Net-(PAD35-P)") (class "Default")
      (node (ref "E40") (pin "15") (pinfunction "15_15") (pintype "passive"))
      (node (ref "PAD35") (pin "1") (pinfunction "P_1") (pintype "passive"))
    )
    (net (code "127") (name "Net-(PAD36-P)") (class "Default")
      (node (ref "E40") (pin "14") (pinfunction "14_14") (pintype "passive"))
      (node (ref "PAD36") (pin "1") (pinfunction "P_1") (pintype "passive"))
    )
    (net (code "128") (name "Net-(PAD37-P)") (class "Default")
      (node (ref "E40") (pin "13") (pinfunction "13_13") (pintype "passive"))
      (node (ref "PAD37") (pin "1") (pinfunction "P_1") (pintype "passive"))
    )
    (net (code "129") (name "Net-(PAD38-P)") (class "Default")
      (node (ref "E40") (pin "12") (pinfunction "12_12") (pintype "passive"))
      (node (ref "PAD38") (pin "1") (pinfunction "P_1") (pintype "passive"))
    )
    (net (code "130") (name "Net-(PAD39-P)") (class "Default")
      (node (ref "E40") (pin "11") (pinfunction "11_11") (pintype "passive"))
      (node (ref "PAD39") (pin "1") (pinfunction "P_1") (pintype "passive"))
    )
    (net (code "131") (name "Net-(PAD40-P)") (class "Default")
      (node (ref "E40") (pin "10") (pinfunction "10_10") (pintype "passive"))
      (node (ref "PAD40") (pin "1") (pinfunction "P_1") (pintype "passive"))
    )
    (net (code "132") (name "Net-(PAD41-P)") (class "Default")
      (node (ref "E40") (pin "9") (pinfunction "9_9") (pintype "passive"))
      (node (ref "PAD41") (pin "1") (pinfunction "P_1") (pintype "passive"))
    )
    (net (code "133") (name "Net-(PAD42-P)") (class "Default")
      (node (ref "E39") (pin "1") (pinfunction "1_1") (pintype "passive"))
      (node (ref "PAD42") (pin "1") (pinfunction "P_1") (pintype "passive"))
    )
    (net (code "134") (name "Net-(PAD43-P)") (class "Default")
      (node (ref "E39") (pin "2") (pinfunction "2_2") (pintype "passive"))
      (node (ref "PAD43") (pin "1") (pinfunction "P_1") (pintype "passive"))
    )
    (net (code "135") (name "Net-(PAD44-P)") (class "Default")
      (node (ref "E39") (pin "3") (pinfunction "3_3") (pintype "passive"))
      (node (ref "PAD44") (pin "1") (pinfunction "P_1") (pintype "passive"))
    )
    (net (code "136") (name "Net-(PAD45-P)") (class "Default")
      (node (ref "E39") (pin "4") (pinfunction "4_4") (pintype "passive"))
      (node (ref "PAD45") (pin "1") (pinfunction "P_1") (pintype "passive"))
    )
    (net (code "137") (name "Net-(PAD46-P)") (class "Default")
      (node (ref "E39") (pin "5") (pinfunction "5_5") (pintype "passive"))
      (node (ref "PAD46") (pin "1") (pinfunction "P_1") (pintype "passive"))
    )
    (net (code "138") (name "Net-(PAD47-P)") (class "Default")
      (node (ref "E39") (pin "6") (pinfunction "6_6") (pintype "passive"))
      (node (ref "PAD47") (pin "1") (pinfunction "P_1") (pintype "passive"))
    )
    (net (code "139") (name "Net-(PAD48-P)") (class "Default")
      (node (ref "E39") (pin "7") (pinfunction "7_7") (pintype "passive"))
      (node (ref "PAD48") (pin "1") (pinfunction "P_1") (pintype "passive"))
    )
    (net (code "140") (name "Net-(PAD49-P)") (class "Default")
      (node (ref "E39") (pin "8") (pinfunction "8_8") (pintype "passive"))
      (node (ref "PAD49") (pin "1") (pinfunction "P_1") (pintype "passive"))
    )
    (net (code "141") (name "Net-(PAD50-P)") (class "Default")
      (node (ref "E39") (pin "16") (pinfunction "16_16") (pintype "passive"))
      (node (ref "PAD50") (pin "1") (pinfunction "P_1") (pintype "passive"))
    )
    (net (code "142") (name "Net-(PAD51-P)") (class "Default")
      (node (ref "E39") (pin "15") (pinfunction "15_15") (pintype "passive"))
      (node (ref "PAD51") (pin "1") (pinfunction "P_1") (pintype "passive"))
    )
    (net (code "143") (name "Net-(PAD52-P)") (class "Default")
      (node (ref "E39") (pin "14") (pinfunction "14_14") (pintype "passive"))
      (node (ref "PAD52") (pin "1") (pinfunction "P_1") (pintype "passive"))
    )
    (net (code "144") (name "Net-(PAD53-P)") (class "Default")
      (node (ref "E39") (pin "13") (pinfunction "13_13") (pintype "passive"))
      (node (ref "PAD53") (pin "1") (pinfunction "P_1") (pintype "passive"))
    )
    (net (code "145") (name "Net-(PAD54-P)") (class "Default")
      (node (ref "E39") (pin "12") (pinfunction "12_12") (pintype "passive"))
      (node (ref "PAD54") (pin "1") (pinfunction "P_1") (pintype "passive"))
    )
    (net (code "146") (name "Net-(PAD55-P)") (class "Default")
      (node (ref "E39") (pin "11") (pinfunction "11_11") (pintype "passive"))
      (node (ref "PAD55") (pin "1") (pinfunction "P_1") (pintype "passive"))
    )
    (net (code "147") (name "Net-(PAD56-P)") (class "Default")
      (node (ref "E39") (pin "10") (pinfunction "10_10") (pintype "passive"))
      (node (ref "PAD56") (pin "1") (pinfunction "P_1") (pintype "passive"))
    )
    (net (code "148") (name "Net-(PAD57-P)") (class "Default")
      (node (ref "E39") (pin "9") (pinfunction "9_9") (pintype "passive"))
      (node (ref "PAD57") (pin "1") (pinfunction "P_1") (pintype "passive"))
    )
    (net (code "149") (name "PARITY") (class "Default")
      (node (ref "E15") (pin "1") (pinfunction "I0_1") (pintype "input"))
      (node (ref "E15") (pin "13") (pinfunction "I1_13") (pintype "input"))
      (node (ref "E15") (pin "2") (pinfunction "I1_2") (pintype "input"))
      (node (ref "E4") (pin "15") (pinfunction "RCO_15") (pintype "output"))
    )
    (net (code "150") (name "RD") (class "Default")
      (node (ref "E25") (pin "1") (pinfunction "I_1") (pintype "input"))
      (node (ref "E32") (pin "10") (pinfunction "I1_10") (pintype "input"))
      (node (ref "E35") (pin "10") (pinfunction "O_10") (pintype "output"))
    )
    (net (code "151") (name "RUN") (class "Default")
      (node (ref "E18") (pin "11") (pinfunction "I0_11") (pintype "input"))
      (node (ref "E30") (pin "9") (pinfunction "Q_9") (pintype "output"))
      (node (ref "IC9") (pin "6") (pinfunction "I0_6") (pintype "input"))
      (node (ref "IC9") (pin "7") (pinfunction "I1_7") (pintype "input"))
    )
    (net (code "152") (name "RX_DATA") (class "Default")
      (node (ref "E22") (pin "2") (pinfunction "J_2") (pintype "input"))
      (node (ref "E22") (pin "3") (pinfunction "K_3") (pintype "input"))
      (node (ref "E35") (pin "1") (pinfunction "O_1") (pintype "output"))
    )
    (net (code "153") (name "SHIFT") (class "Default")
      (node (ref "E32") (pin "3") (pinfunction "I0_3") (pintype "input"))
      (node (ref "E35") (pin "4") (pinfunction "O_4") (pintype "output"))
    )
    (net (code "154") (name "TR_SKIP") (class "Default")
      (node (ref "E18") (pin "1") (pinfunction "O_1") (pintype "output"))
      (node (ref "E19") (pin "16") (pinfunction "K_16") (pintype "input"))
      (node (ref "E20") (pin "1") (pinfunction "I0_1") (pintype "input"))
      (node (ref "E26") (pin "2") (pinfunction "I1_2") (pintype "input"))
    )
    (net (code "155") (name "VCC") (class "Default")
      (node (ref "C1") (pin "1") (pinfunction "1_1") (pintype "passive"))
      (node (ref "C10") (pin "1") (pinfunction "1_1") (pintype "passive"))
      (node (ref "C11") (pin "1") (pinfunction "1_1") (pintype "passive"))
      (node (ref "C12") (pin "1") (pinfunction "1_1") (pintype "passive"))
      (node (ref "C13") (pin "1") (pinfunction "1_1") (pintype "passive"))
      (node (ref "C14") (pin "1") (pinfunction "1_1") (pintype "passive"))
      (node (ref "C15") (pin "1") (pinfunction "1_1") (pintype "passive"))
      (node (ref "C16") (pin "1") (pinfunction "1_1") (pintype "passive"))
      (node (ref "C17") (pin "1") (pinfunction "1_1") (pintype "passive"))
      (node (ref "C18") (pin "1") (pinfunction "1_1") (pintype "passive"))
      (node (ref "C19") (pin "1") (pinfunction "1_1") (pintype "passive"))
      (node (ref "C2") (pin "1") (pinfunction "1_1") (pintype "passive"))
      (node (ref "C20") (pin "1") (pinfunction "1_1") (pintype "passive"))
      (node (ref "C21") (pin "1") (pinfunction "1_1") (pintype "passive"))
      (node (ref "C22") (pin "1") (pinfunction "1_1") (pintype "passive"))
      (node (ref "C23") (pin "1") (pinfunction "1_1") (pintype "passive"))
      (node (ref "C24") (pin "1") (pinfunction "1_1") (pintype "passive"))
      (node (ref "C25") (pin "1") (pinfunction "1_1") (pintype "passive"))
      (node (ref "C26") (pin "1") (pinfunction "1_1") (pintype "passive"))
      (node (ref "C27") (pin "1") (pinfunction "1_1") (pintype "passive"))
      (node (ref "C28") (pin "1") (pinfunction "1_1") (pintype "passive"))
      (node (ref "C29") (pin "1") (pinfunction "1_1") (pintype "passive"))
      (node (ref "C3") (pin "1") (pinfunction "1_1") (pintype "passive"))
      (node (ref "C30") (pin "1") (pinfunction "1_1") (pintype "passive"))
      (node (ref "C31") (pin "1") (pinfunction "1_1") (pintype "passive"))
      (node (ref "C32") (pin "1") (pinfunction "1_1") (pintype "passive"))
      (node (ref "C33") (pin "1") (pinfunction "1_1") (pintype "passive"))
      (node (ref "C34") (pin "1") (pinfunction "1_1") (pintype "passive"))
      (node (ref "C35") (pin "1") (pinfunction "1_1") (pintype "passive"))
      (node (ref "C36") (pin "1") (pinfunction "1_1") (pintype "passive"))
      (node (ref "C37") (pin "1") (pinfunction "1_1") (pintype "passive"))
      (node (ref "C38") (pin "1") (pinfunction "1_1") (pintype "passive"))
      (node (ref "C39") (pin "1") (pinfunction "1_1") (pintype "passive"))
      (node (ref "C4") (pin "1") (pinfunction "1_1") (pintype "passive"))
      (node (ref "C40") (pin "+") (pinfunction "+_+") (pintype "passive"))
      (node (ref "C5") (pin "1") (pinfunction "1_1") (pintype "passive"))
      (node (ref "C6") (pin "1") (pinfunction "1_1") (pintype "passive"))
      (node (ref "C7") (pin "1") (pinfunction "1_1") (pintype "passive"))
      (node (ref "C8") (pin "1") (pinfunction "1_1") (pintype "passive"))
      (node (ref "C9") (pin "1") (pinfunction "1_1") (pintype "passive"))
      (node (ref "E14") (pin "6") (pinfunction "G1_6") (pintype "input"))
      (node (ref "E16") (pin "10") (pinfunction "PRE_10") (pintype "input"))
      (node (ref "E16") (pin "4") (pinfunction "PRE_4") (pintype "input"))
      (node (ref "E17") (pin "7") (pinfunction "PRE_7") (pintype "input"))
      (node (ref "E2") (pin "1") (pinfunction "CLR_1") (pintype "input"))
      (node (ref "E2") (pin "10") (pinfunction "PRE_10") (pintype "input"))
      (node (ref "E2") (pin "11") (pinfunction "CLK_11") (pintype "input"))
      (node (ref "E2") (pin "12") (pinfunction "D_12") (pintype "input"))
      (node (ref "E2") (pin "13") (pinfunction "CLR_13") (pintype "input"))
      (node (ref "E20") (pin "10") (pinfunction "I1_10") (pintype "input"))
      (node (ref "E20") (pin "9") (pinfunction "I0_9") (pintype "input"))
      (node (ref "E25") (pin "11") (pinfunction "I_11") (pintype "input"))
      (node (ref "E25") (pin "13") (pinfunction "I_13") (pintype "input"))
      (node (ref "E30") (pin "10") (pinfunction "PRE_10") (pintype "input"))
      (node (ref "E30") (pin "12") (pinfunction "D_12") (pintype "input"))
      (node (ref "E30") (pin "4") (pinfunction "PRE_4") (pintype "input"))
      (node (ref "R1") (pin "2") (pinfunction "2_2") (pintype "passive"))
      (node (ref "R18") (pin "2") (pinfunction "2_2") (pintype "passive"))
      (node (ref "R19") (pin "1") (pinfunction "1_1") (pintype "passive"))
      (node (ref "R2") (pin "2") (pinfunction "2_2") (pintype "passive"))
      (node (ref "R20") (pin "2") (pinfunction "2_2") (pintype "passive"))
      (node (ref "R3") (pin "2") (pinfunction "2_2") (pintype "passive"))
      (node (ref "R4") (pin "2") (pinfunction "2_2") (pintype "passive"))
      (node (ref "R5") (pin "2") (pinfunction "2_2") (pintype "passive"))
      (node (ref "R6") (pin "2") (pinfunction "2_2") (pintype "passive"))
      (node (ref "R7") (pin "2") (pinfunction "2_2") (pintype "passive"))
      (node (ref "R8") (pin "2") (pinfunction "2_2") (pintype "passive"))
      (node (ref "R9") (pin "2") (pinfunction "2_2") (pintype "passive"))
      (node (ref "SL1") (pin "1") (pinfunction "S_1") (pintype "passive"))
    )
    (net (code "156") (name "WRT") (class "Default")
      (node (ref "E10") (pin "5") (pinfunction "I2_5") (pintype "input"))
      (node (ref "E15") (pin "10") (pinfunction "I1_10") (pintype "input"))
      (node (ref "E25") (pin "2") (pinfunction "O_2") (pintype "output"))
      (node (ref "IC7") (pin "6") (pinfunction "I0_6") (pintype "input"))
    )
    (net (code "157") (name "XDR2") (class "Default")
      (node (ref "E10") (pin "2") (pinfunction "I1_2") (pintype "input"))
      (node (ref "E5") (pin "12") (pinfunction "I0_12") (pintype "input"))
      (node (ref "E5") (pin "8") (pinfunction "O_8") (pintype "output"))
    )
    (net (code "158") (name "XFER_REQ") (class "Default")
      (node (ref "E19") (pin "4") (pinfunction "J_4") (pintype "input"))
      (node (ref "E20") (pin "12") (pinfunction "I0_12") (pintype "input"))
      (node (ref "E26") (pin "1") (pinfunction "I0_1") (pintype "input"))
      (node (ref "E36") (pin "4") (pinfunction "O_4") (pintype "output"))
    )
    (net (code "159") (name "unconnected-(D34L1-2-PadB)") (class "Default")
      (node (ref "D34L1") (pin "B") (pinfunction "2_B") (pintype "passive"))
    )
    (net (code "160") (name "unconnected-(D34L1-34-PadNN)") (class "Default")
      (node (ref "D34L1") (pin "NN") (pinfunction "34_NN") (pintype "passive"))
    )
    (net (code "161") (name "unconnected-(D34L1-38-PadTT)") (class "Default")
      (node (ref "D34L1") (pin "TT") (pinfunction "38_TT") (pintype "passive"))
    )
    (net (code "162") (name "unconnected-(D34L1-40-PadVV)") (class "Default")
      (node (ref "D34L1") (pin "VV") (pinfunction "40_VV") (pintype "passive"))
    )
    (net (code "163") (name "unconnected-(D34L2-2-PadB)") (class "Default")
      (node (ref "D34L2") (pin "B") (pinfunction "2_B") (pintype "passive"))
    )
    (net (code "164") (name "unconnected-(D34L2-34-PadNN)") (class "Default")
      (node (ref "D34L2") (pin "NN") (pinfunction "34_NN") (pintype "passive"))
    )
    (net (code "165") (name "unconnected-(D34L2-38-PadTT)") (class "Default")
      (node (ref "D34L2") (pin "TT") (pinfunction "38_TT") (pintype "passive"))
    )
    (net (code "166") (name "unconnected-(D34L2-40-PadVV)") (class "Default")
      (node (ref "D34L2") (pin "VV") (pinfunction "40_VV") (pintype "passive"))
    )
    (net (code "167") (name "unconnected-(D35L1-2-PadB)") (class "Default")
      (node (ref "D35L1") (pin "B") (pinfunction "2_B") (pintype "passive"))
    )
    (net (code "168") (name "unconnected-(D35L1-40-PadVV)") (class "Default")
      (node (ref "D35L1") (pin "VV") (pinfunction "40_VV") (pintype "passive"))
    )
    (net (code "169") (name "unconnected-(D35L2-2-PadB)") (class "Default")
      (node (ref "D35L2") (pin "B") (pinfunction "2_B") (pintype "passive"))
    )
    (net (code "170") (name "unconnected-(D35L2-40-PadVV)") (class "Default")
      (node (ref "D35L2") (pin "VV") (pinfunction "40_VV") (pintype "passive"))
    )
    (net (code "171") (name "unconnected-(D36L1-2-PadB)") (class "Default")
      (node (ref "D36L1") (pin "B") (pinfunction "2_B") (pintype "passive"))
    )
    (net (code "172") (name "unconnected-(D36L1-40-PadVV)") (class "Default")
      (node (ref "D36L1") (pin "VV") (pinfunction "40_VV") (pintype "passive"))
    )
    (net (code "173") (name "unconnected-(D36L2-2-PadB)") (class "Default")
      (node (ref "D36L2") (pin "B") (pinfunction "2_B") (pintype "passive"))
    )
    (net (code "174") (name "unconnected-(D36L2-40-PadVV)") (class "Default")
      (node (ref "D36L2") (pin "VV") (pinfunction "40_VV") (pintype "passive"))
    )
    (net (code "175") (name "unconnected-(E2A-Q-Pad5)") (class "Default")
      (node (ref "E2") (pin "5") (pinfunction "Q_5") (pintype "output"))
    )
    (net (code "176") (name "unconnected-(E2B-Q-Pad9)") (class "Default")
      (node (ref "E2") (pin "9") (pinfunction "Q_9") (pintype "output"))
    )
    (net (code "177") (name "unconnected-(E2B-~{Q}-Pad8)") (class "Default")
      (node (ref "E2") (pin "8") (pinfunction "~{Q}_8") (pintype "output"))
    )
    (net (code "178") (name "unconnected-(E4A-QA-Pad14)") (class "Default")
      (node (ref "E4") (pin "14") (pinfunction "QA_14") (pintype "output"))
    )
    (net (code "179") (name "unconnected-(E4A-QB-Pad13)") (class "Default")
      (node (ref "E4") (pin "13") (pinfunction "QB_13") (pintype "output"))
    )
    (net (code "180") (name "unconnected-(E4A-QC-Pad12)") (class "Default")
      (node (ref "E4") (pin "12") (pinfunction "QC_12") (pintype "output"))
    )
    (net (code "181") (name "unconnected-(E4A-QD-Pad11)") (class "Default")
      (node (ref "E4") (pin "11") (pinfunction "QD_11") (pintype "output"))
    )
    (net (code "182") (name "unconnected-(E11A-Y0-Pad15)") (class "Default")
      (node (ref "E11") (pin "15") (pinfunction "Y0_15") (pintype "output"))
    )
    (net (code "183") (name "unconnected-(E11A-Y2-Pad13)") (class "Default")
      (node (ref "E11") (pin "13") (pinfunction "Y2_13") (pintype "output"))
    )
    (net (code "184") (name "unconnected-(E11A-Y3-Pad12)") (class "Default")
      (node (ref "E11") (pin "12") (pinfunction "Y3_12") (pintype "output"))
    )
    (net (code "185") (name "unconnected-(E11A-Y4-Pad11)") (class "Default")
      (node (ref "E11") (pin "11") (pinfunction "Y4_11") (pintype "output"))
    )
    (net (code "186") (name "unconnected-(E11A-Y5-Pad10)") (class "Default")
      (node (ref "E11") (pin "10") (pinfunction "Y5_10") (pintype "output"))
    )
    (net (code "187") (name "unconnected-(E11A-Y6-Pad9)") (class "Default")
      (node (ref "E11") (pin "9") (pinfunction "Y6_9") (pintype "output"))
    )
    (net (code "188") (name "unconnected-(E12A-Y0-Pad15)") (class "Default")
      (node (ref "E12") (pin "15") (pinfunction "Y0_15") (pintype "output"))
    )
    (net (code "189") (name "unconnected-(E12A-Y1-Pad14)") (class "Default")
      (node (ref "E12") (pin "14") (pinfunction "Y1_14") (pintype "output"))
    )
    (net (code "190") (name "unconnected-(E12A-Y4-Pad11)") (class "Default")
      (node (ref "E12") (pin "11") (pinfunction "Y4_11") (pintype "output"))
    )
    (net (code "191") (name "unconnected-(E12A-Y5-Pad10)") (class "Default")
      (node (ref "E12") (pin "10") (pinfunction "Y5_10") (pintype "output"))
    )
    (net (code "192") (name "unconnected-(E12A-Y6-Pad9)") (class "Default")
      (node (ref "E12") (pin "9") (pinfunction "Y6_9") (pintype "output"))
    )
    (net (code "193") (name "unconnected-(E12A-Y7-Pad7)") (class "Default")
      (node (ref "E12") (pin "7") (pinfunction "Y7_7") (pintype "output"))
    )
    (net (code "194") (name "unconnected-(E13A-Y0-Pad15)") (class "Default")
      (node (ref "E13") (pin "15") (pinfunction "Y0_15") (pintype "output"))
    )
    (net (code "195") (name "unconnected-(E13A-Y1-Pad14)") (class "Default")
      (node (ref "E13") (pin "14") (pinfunction "Y1_14") (pintype "output"))
    )
    (net (code "196") (name "unconnected-(E13A-Y2-Pad13)") (class "Default")
      (node (ref "E13") (pin "13") (pinfunction "Y2_13") (pintype "output"))
    )
    (net (code "197") (name "unconnected-(E13A-Y3-Pad12)") (class "Default")
      (node (ref "E13") (pin "12") (pinfunction "Y3_12") (pintype "output"))
    )
    (net (code "198") (name "unconnected-(E17B-Q-Pad11)") (class "Default")
      (node (ref "E17") (pin "11") (pinfunction "Q_11") (pintype "output"))
    )
    (net (code "199") (name "unconnected-(E19A-Q-Pad15)") (class "Default")
      (node (ref "E19") (pin "15") (pinfunction "Q_15") (pintype "output"))
    )
    (net (code "200") (name "unconnected-(E19B-Q-Pad11)") (class "Default")
      (node (ref "E19") (pin "11") (pinfunction "Q_11") (pintype "output"))
    )
    (net (code "201") (name "unconnected-(E20C-O-Pad8)") (class "Default")
      (node (ref "E20") (pin "8") (pinfunction "O_8") (pintype "output"))
    )
    (net (code "202") (name "unconnected-(E21A-~{QD}-Pad11)") (class "Default")
      (node (ref "E21") (pin "11") (pinfunction "~{QD}_11") (pintype "output"))
    )
    (net (code "203") (name "unconnected-(E22A-~{QD}-Pad11)") (class "Default")
      (node (ref "E22") (pin "11") (pinfunction "~{QD}_11") (pintype "output"))
    )
    (net (code "204") (name "unconnected-(E23A-~{QD}-Pad11)") (class "Default")
      (node (ref "E23") (pin "11") (pinfunction "~{QD}_11") (pintype "output"))
    )
    (net (code "205") (name "unconnected-(E26D-O-Pad11)") (class "Default")
      (node (ref "E26") (pin "11") (pinfunction "O_11") (pintype "output"))
    )
    (net (code "206") (name "unconnected-(E30A-~{Q}-Pad6)") (class "Default")
      (node (ref "E30") (pin "6") (pinfunction "~{Q}_6") (pintype "output"))
    )
    (net (code "207") (name "unconnected-(E30B-~{Q}-Pad8)") (class "Default")
      (node (ref "E30") (pin "8") (pinfunction "~{Q}_8") (pintype "output"))
    )
    (net (code "208") (name "unconnected-(E36D-O-Pad13)") (class "Default")
      (node (ref "E36") (pin "13") (pinfunction "O_13") (pintype "output"))
    )
    (net (code "209") (name "unconnected-(LASTDEV-Pad8)") (class "Default")
      (node (ref "LASTDEV") (pin "8") (pinfunction "8_8") (pintype "passive"))
    )
    (net (code "210") (name "unconnected-(LASTDEV-Pad9)") (class "Default")
      (node (ref "LASTDEV") (pin "9") (pinfunction "9_9") (pintype "passive"))
    )
    (net (code "211") (name "unconnected-(LASTDEV-Pad10)") (class "Default")
      (node (ref "LASTDEV") (pin "10") (pinfunction "10_10") (pintype "passive"))
    )
    (net (code "212") (name "~{ACB00}") (class "Default")
      (node (ref "D34L1") (pin "D") (pinfunction "4_D") (pintype "passive"))
      (node (ref "D34L2") (pin "D") (pinfunction "4_D") (pintype "passive"))
      (node (ref "IC6") (pin "3") (pinfunction "O_3") (pintype "open_collector"))
    )
    (net (code "213") (name "~{ACB01}") (class "Default")
      (node (ref "D34L1") (pin "J") (pinfunction "8_J") (pintype "passive"))
      (node (ref "D34L2") (pin "J") (pinfunction "8_J") (pintype "passive"))
      (node (ref "IC6") (pin "5") (pinfunction "O_5") (pintype "open_collector"))
    )
    (net (code "214") (name "~{ACB02}") (class "Default")
      (node (ref "D34L1") (pin "N") (pinfunction "12_N") (pintype "passive"))
      (node (ref "D34L2") (pin "N") (pinfunction "12_N") (pintype "passive"))
      (node (ref "IC1") (pin "3") (pinfunction "O_3") (pintype "open_collector"))
    )
    (net (code "215") (name "~{ACB03}") (class "Default")
      (node (ref "D34L1") (pin "T") (pinfunction "16_T") (pintype "passive"))
      (node (ref "D34L2") (pin "T") (pinfunction "16_T") (pintype "passive"))
      (node (ref "IC2") (pin "5") (pinfunction "O_5") (pintype "open_collector"))
    )
    (net (code "216") (name "~{ACB04}") (class "Default")
      (node (ref "D34L1") (pin "X") (pinfunction "20_X") (pintype "passive"))
      (node (ref "D34L2") (pin "X") (pinfunction "20_X") (pintype "passive"))
      (node (ref "IC1") (pin "5") (pinfunction "O_5") (pintype "open_collector"))
    )
    (net (code "217") (name "~{ACB05}") (class "Default")
      (node (ref "D34L1") (pin "BB") (pinfunction "24_BB") (pintype "passive"))
      (node (ref "D34L2") (pin "BB") (pinfunction "24_BB") (pintype "passive"))
      (node (ref "IC4") (pin "3") (pinfunction "O_3") (pintype "open_collector"))
    )
    (net (code "218") (name "~{ACB06}") (class "Default")
      (node (ref "D34L1") (pin "FF") (pinfunction "28_FF") (pintype "passive"))
      (node (ref "D34L2") (pin "FF") (pinfunction "28_FF") (pintype "passive"))
      (node (ref "IC3") (pin "3") (pinfunction "O_3") (pintype "open_collector"))
    )
    (net (code "219") (name "~{ACB07}") (class "Default")
      (node (ref "D34L1") (pin "LL") (pinfunction "32_LL") (pintype "passive"))
      (node (ref "D34L2") (pin "LL") (pinfunction "32_LL") (pintype "passive"))
      (node (ref "IC3") (pin "5") (pinfunction "O_5") (pintype "open_collector"))
    )
    (net (code "220") (name "~{ACB08}") (class "Default")
      (node (ref "D34L1") (pin "RR") (pinfunction "36_RR") (pintype "passive"))
      (node (ref "D34L2") (pin "RR") (pinfunction "36_RR") (pintype "passive"))
      (node (ref "IC4") (pin "5") (pinfunction "O_5") (pintype "open_collector"))
    )
    (net (code "221") (name "~{ACB09}") (class "Default")
      (node (ref "D34L1") (pin "F") (pinfunction "6_F") (pintype "passive"))
      (node (ref "D34L2") (pin "F") (pinfunction "6_F") (pintype "passive"))
      (node (ref "IC5") (pin "3") (pinfunction "O_3") (pintype "open_collector"))
    )
    (net (code "222") (name "~{ACB10}") (class "Default")
      (node (ref "D34L1") (pin "L") (pinfunction "10_L") (pintype "passive"))
      (node (ref "D34L2") (pin "L") (pinfunction "10_L") (pintype "passive"))
      (node (ref "IC5") (pin "5") (pinfunction "O_5") (pintype "open_collector"))
    )
    (net (code "223") (name "~{ACB11}") (class "Default")
      (node (ref "D34L1") (pin "R") (pinfunction "14_R") (pintype "passive"))
      (node (ref "D34L2") (pin "R") (pinfunction "14_R") (pintype "passive"))
      (node (ref "IC2") (pin "3") (pinfunction "O_3") (pintype "open_collector"))
    )
    (net (code "224") (name "~{ACCLEAR}") (class "Default")
      (node (ref "D34L1") (pin "DD") (pinfunction "26_DD") (pintype "passive"))
      (node (ref "D34L2") (pin "DD") (pinfunction "26_DD") (pintype "passive"))
      (node (ref "IC7") (pin "3") (pinfunction "O_3") (pintype "open_collector"))
    )
    (net (code "225") (name "~{BMB03}") (class "Default")
      (node (ref "D35L1") (pin "T") (pinfunction "16_T") (pintype "passive"))
      (node (ref "D35L2") (pin "T") (pinfunction "16_T") (pintype "passive"))
    )
    (net (code "226") (name "~{BMB04}") (class "Default")
      (node (ref "D35L1") (pin "BB") (pinfunction "24_BB") (pintype "passive"))
      (node (ref "D35L2") (pin "BB") (pinfunction "24_BB") (pintype "passive"))
    )
    (net (code "227") (name "~{BMB05}") (class "Default")
      (node (ref "D35L1") (pin "LL") (pinfunction "32_LL") (pintype "passive"))
      (node (ref "D35L2") (pin "LL") (pinfunction "32_LL") (pintype "passive"))
    )
    (net (code "228") (name "~{BMB06}") (class "Default")
      (node (ref "D35L1") (pin "F") (pinfunction "6_F") (pintype "passive"))
      (node (ref "D35L2") (pin "F") (pinfunction "6_F") (pintype "passive"))
    )
    (net (code "229") (name "~{BMB07}") (class "Default")
      (node (ref "D35L1") (pin "R") (pinfunction "14_R") (pintype "passive"))
      (node (ref "D35L2") (pin "R") (pinfunction "14_R") (pintype "passive"))
    )
    (net (code "230") (name "~{BMB08}") (class "Default")
      (node (ref "D35L1") (pin "Z") (pinfunction "22_Z") (pintype "passive"))
      (node (ref "D35L2") (pin "Z") (pinfunction "22_Z") (pintype "passive"))
    )
    (net (code "231") (name "~{BRUN}") (class "Default")
      (node (ref "D34L1") (pin "JJ") (pinfunction "30_JJ") (pintype "passive"))
      (node (ref "D34L2") (pin "JJ") (pinfunction "30_JJ") (pintype "passive"))
    )
    (net (code "232") (name "~{CLK_PARITY}") (class "Default")
      (node (ref "E17") (pin "6") (pinfunction "CLK_6") (pintype "input"))
      (node (ref "E32") (pin "6") (pinfunction "O_6") (pintype "output"))
      (node (ref "E5") (pin "4") (pinfunction "I0_4") (pintype "input"))
      (node (ref "E5") (pin "5") (pinfunction "I1_5") (pintype "input"))
    )
    (net (code "233") (name "~{DONE}") (class "Default")
      (node (ref "E10") (pin "4") (pinfunction "I1_4") (pintype "input"))
      (node (ref "E25") (pin "4") (pinfunction "O_4") (pintype "output"))
      (node (ref "E31") (pin "12") (pinfunction "I2_12") (pintype "input"))
    )
    (net (code "234") (name "~{ENB_BUF_LD}") (class "Default")
      (node (ref "E21") (pin "9") (pinfunction "S/~{L}_9") (pintype "input"))
      (node (ref "E22") (pin "9") (pinfunction "S/~{L}_9") (pintype "input"))
      (node (ref "E23") (pin "9") (pinfunction "S/~{L}_9") (pintype "input"))
      (node (ref "E24") (pin "11") (pinfunction "O_11") (pintype "output"))
      (node (ref "E32") (pin "13") (pinfunction "I2_13") (pintype "input"))
      (node (ref "E32") (pin "2") (pinfunction "I1_2") (pintype "input"))
      (node (ref "E4") (pin "9") (pinfunction "LD_9") (pintype "input"))
    )
    (net (code "235") (name "~{INIT1}") (class "Default")
      (node (ref "E11") (pin "7") (pinfunction "Y7_7") (pintype "output"))
      (node (ref "E2") (pin "4") (pinfunction "PRE_4") (pintype "input"))
    )
    (net (code "236") (name "~{INIT4}") (class "Default")
      (node (ref "E13") (pin "7") (pinfunction "Y7_7") (pintype "output"))
      (node (ref "E2") (pin "3") (pinfunction "CLK_3") (pintype "input"))
    )
    (net (code "237") (name "~{INIT}") (class "Default")
      (node (ref "E15") (pin "6") (pinfunction "O_6") (pintype "output"))
      (node (ref "E16") (pin "1") (pinfunction "CLR_1") (pintype "input"))
      (node (ref "E16") (pin "13") (pinfunction "CLR_13") (pintype "input"))
      (node (ref "E17") (pin "3") (pinfunction "CLR_3") (pintype "input"))
      (node (ref "E19") (pin "3") (pinfunction "CLR_3") (pintype "input"))
      (node (ref "E19") (pin "8") (pinfunction "CLR_8") (pintype "input"))
      (node (ref "E21") (pin "1") (pinfunction "CLR_1") (pintype "input"))
      (node (ref "E22") (pin "1") (pinfunction "CLR_1") (pintype "input"))
      (node (ref "E23") (pin "1") (pinfunction "CLR_1") (pintype "input"))
      (node (ref "E24") (pin "9") (pinfunction "I0_9") (pintype "input"))
      (node (ref "E30") (pin "1") (pinfunction "CLR_1") (pintype "input"))
      (node (ref "E4") (pin "1") (pinfunction "CLR_1") (pintype "input"))
    )
    (net (code "238") (name "~{INTR4}") (class "Default")
      (node (ref "E13") (pin "9") (pinfunction "Y6_9") (pintype "output"))
      (node (ref "E30") (pin "3") (pinfunction "CLK_3") (pintype "input"))
    )
    (net (code "239") (name "~{INT_RQ}") (class "Default")
      (node (ref "D34L1") (pin "Z") (pinfunction "22_Z") (pintype "passive"))
      (node (ref "D34L2") (pin "Z") (pinfunction "22_Z") (pintype "passive"))
      (node (ref "IC10") (pin "5") (pinfunction "O_5") (pintype "open_collector"))
    )
    (net (code "240") (name "~{IOS}") (class "Default")
      (node (ref "D34L1") (pin "V") (pinfunction "18_V") (pintype "passive"))
      (node (ref "D34L2") (pin "V") (pinfunction "18_V") (pintype "passive"))
      (node (ref "IC10") (pin "3") (pinfunction "O_3") (pintype "open_collector"))
    )
    (net (code "241") (name "~{LCD1}") (class "Default")
      (node (ref "E10") (pin "9") (pinfunction "I0_9") (pintype "input"))
      (node (ref "E11") (pin "14") (pinfunction "Y1_14") (pintype "output"))
      (node (ref "E16") (pin "11") (pinfunction "CLK_11") (pintype "input"))
      (node (ref "E16") (pin "3") (pinfunction "CLK_3") (pintype "input"))
      (node (ref "E24") (pin "5") (pinfunction "I1_5") (pintype "input"))
      (node (ref "E25") (pin "5") (pinfunction "I_5") (pintype "input"))
    )
    (net (code "242") (name "~{MAINT}") (class "Default")
      (node (ref "E10") (pin "3") (pinfunction "I0_3") (pintype "input"))
      (node (ref "E16") (pin "8") (pinfunction "~{Q}_8") (pintype "output"))
      (node (ref "E17") (pin "2") (pinfunction "PRE_2") (pintype "input"))
      (node (ref "E19") (pin "2") (pinfunction "PRE_2") (pintype "input"))
      (node (ref "E19") (pin "7") (pinfunction "PRE_7") (pintype "input"))
      (node (ref "E24") (pin "13") (pinfunction "I1_13") (pintype "input"))
      (node (ref "E31") (pin "5") (pinfunction "I3_5") (pintype "input"))
      (node (ref "E31") (pin "9") (pinfunction "I0_9") (pintype "input"))
    )
    (net (code "243") (name "~{MYDEV}") (class "Default")
      (node (ref "E11") (pin "4") (pinfunction "G2A_4") (pintype "input"))
      (node (ref "E12") (pin "4") (pinfunction "G2A_4") (pintype "input"))
      (node (ref "E13") (pin "4") (pinfunction "G2A_4") (pintype "input"))
      (node (ref "IOT") (pin "1") (pinfunction "P_1") (pintype "passive"))
    )
    (net (code "244") (name "~{PARITY}") (class "Default")
      (node (ref "E15") (pin "12") (pinfunction "I0_12") (pintype "input"))
      (node (ref "E17") (pin "10") (pinfunction "~{Q}_10") (pintype "output"))
    )
    (net (code "245") (name "~{RX_12_BIT}") (class "Default")
      (node (ref "DRIVE") (pin "FF") (pinfunction "28_FF") (pintype "passive"))
      (node (ref "IC8") (pin "3") (pinfunction "O_3") (pintype "open_collector"))
      (node (ref "R16") (pin "2") (pinfunction "2_2") (pintype "passive"))
      (node (ref "R7") (pin "1") (pinfunction "1_1") (pintype "passive"))
    )
    (net (code "246") (name "~{RX_DATA}") (class "Default")
      (node (ref "DRIVE") (pin "BB") (pinfunction "24_BB") (pintype "passive"))
      (node (ref "E35") (pin "2") (pinfunction "I0_2") (pintype "input"))
      (node (ref "IC7") (pin "5") (pinfunction "O_5") (pintype "open_collector"))
      (node (ref "R17") (pin "2") (pinfunction "2_2") (pintype "passive"))
      (node (ref "R8") (pin "1") (pinfunction "1_1") (pintype "passive"))
    )
    (net (code "247") (name "~{RX_DONE}") (class "Default")
      (node (ref "DRIVE") (pin "X") (pinfunction "20_X") (pintype "passive"))
      (node (ref "E36") (pin "8") (pinfunction "I0_8") (pintype "input"))
      (node (ref "R13") (pin "2") (pinfunction "2_2") (pintype "passive"))
      (node (ref "R4") (pin "1") (pinfunction "1_1") (pintype "passive"))
    )
    (net (code "248") (name "~{RX_ERROR}") (class "Default")
      (node (ref "DRIVE") (pin "J") (pinfunction "8_J") (pintype "passive"))
      (node (ref "E36") (pin "3") (pinfunction "I1_3") (pintype "input"))
      (node (ref "R14") (pin "2") (pinfunction "2_2") (pintype "passive"))
      (node (ref "R5") (pin "1") (pinfunction "1_1") (pintype "passive"))
    )
    (net (code "249") (name "~{RX_INIT}") (class "Default")
      (node (ref "DRIVE") (pin "N") (pinfunction "12_N") (pintype "passive"))
      (node (ref "IC8") (pin "5") (pinfunction "O_5") (pintype "open_collector"))
      (node (ref "R20") (pin "1") (pinfunction "1_1") (pintype "passive"))
      (node (ref "R9") (pin "1") (pinfunction "1_1") (pintype "passive"))
    )
    (net (code "250") (name "~{RX_OUT}") (class "Default")
      (node (ref "DRIVE") (pin "RR") (pinfunction "36_RR") (pintype "passive"))
      (node (ref "E35") (pin "8") (pinfunction "I0_8") (pintype "input"))
      (node (ref "R12") (pin "2") (pinfunction "2_2") (pintype "passive"))
      (node (ref "R3") (pin "1") (pinfunction "1_1") (pintype "passive"))
    )
    (net (code "251") (name "~{RX_RUN}") (class "Default")
      (node (ref "DRIVE") (pin "D") (pinfunction "4_D") (pintype "passive"))
      (node (ref "IC9") (pin "5") (pinfunction "O_5") (pintype "open_collector"))
      (node (ref "R15") (pin "2") (pinfunction "2_2") (pintype "passive"))
      (node (ref "R6") (pin "1") (pinfunction "1_1") (pintype "passive"))
    )
    (net (code "252") (name "~{RX_SHIFT}") (class "Default")
      (node (ref "DRIVE") (pin "LL") (pinfunction "32_LL") (pintype "passive"))
      (node (ref "E35") (pin "5") (pinfunction "I0_5") (pintype "input"))
      (node (ref "R10") (pin "2") (pinfunction "2_2") (pintype "passive"))
      (node (ref "R2") (pin "1") (pinfunction "1_1") (pintype "passive"))
    )
    (net (code "253") (name "~{RX_TR_REQ}") (class "Default")
      (node (ref "DRIVE") (pin "T") (pinfunction "16_T") (pintype "passive"))
      (node (ref "E36") (pin "5") (pinfunction "I0_5") (pintype "input"))
      (node (ref "R1") (pin "1") (pinfunction "1_1") (pintype "passive"))
      (node (ref "R11") (pin "2") (pinfunction "2_2") (pintype "passive"))
    )
    (net (code "254") (name "~{SDN4}") (class "Default")
      (node (ref "E13") (pin "10") (pinfunction "Y5_10") (pintype "output"))
      (node (ref "E18") (pin "8") (pinfunction "I0_8") (pintype "input"))
    )
    (net (code "255") (name "~{SER4}") (class "Default")
      (node (ref "E13") (pin "11") (pinfunction "Y4_11") (pintype "output"))
      (node (ref "E18") (pin "5") (pinfunction "I0_5") (pintype "input"))
    )
    (net (code "256") (name "~{STR2}") (class "Default")
      (node (ref "E12") (pin "12") (pinfunction "Y3_12") (pintype "output"))
      (node (ref "E18") (pin "2") (pinfunction "I0_2") (pintype "input"))
    )
    (net (code "257") (name "~{XDR2}") (class "Default")
      (node (ref "E12") (pin "13") (pinfunction "Y2_13") (pintype "output"))
      (node (ref "E24") (pin "4") (pinfunction "I0_4") (pintype "input"))
      (node (ref "E25") (pin "9") (pinfunction "I_9") (pintype "input"))
      (node (ref "E35") (pin "12") (pinfunction "I1_12") (pintype "input"))
      (node (ref "E5") (pin "10") (pinfunction "I1_10") (pintype "input"))
      (node (ref "E5") (pin "9") (pinfunction "I0_9") (pintype "input"))
    )
  )
)
